# OpticalBoardRev2.net
KiCad netlist of a schematic drawn in EAGLE
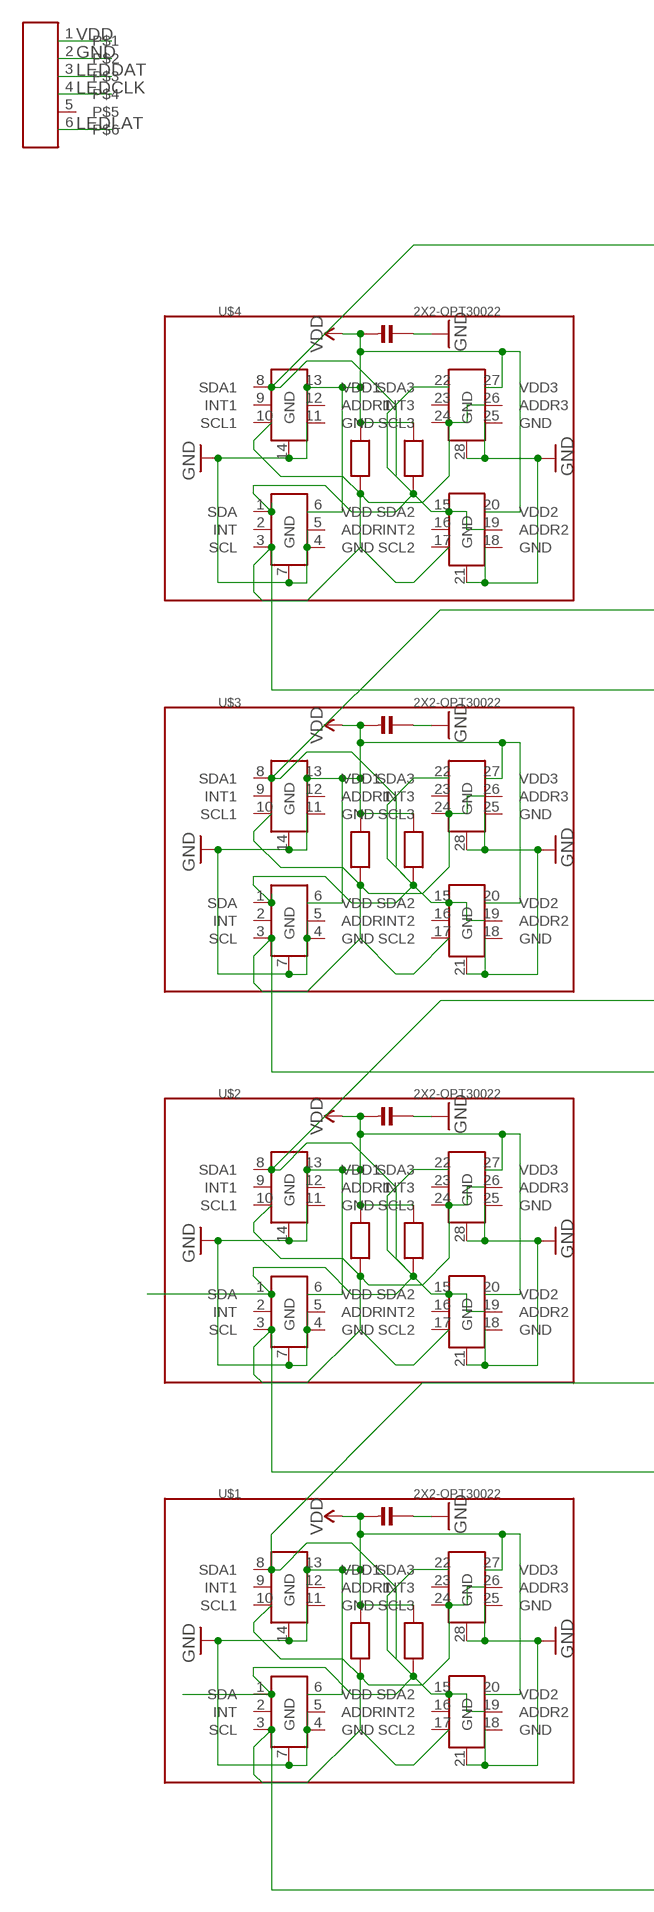
[diagram p0: schematic, sheet 1, part 1 of 2]
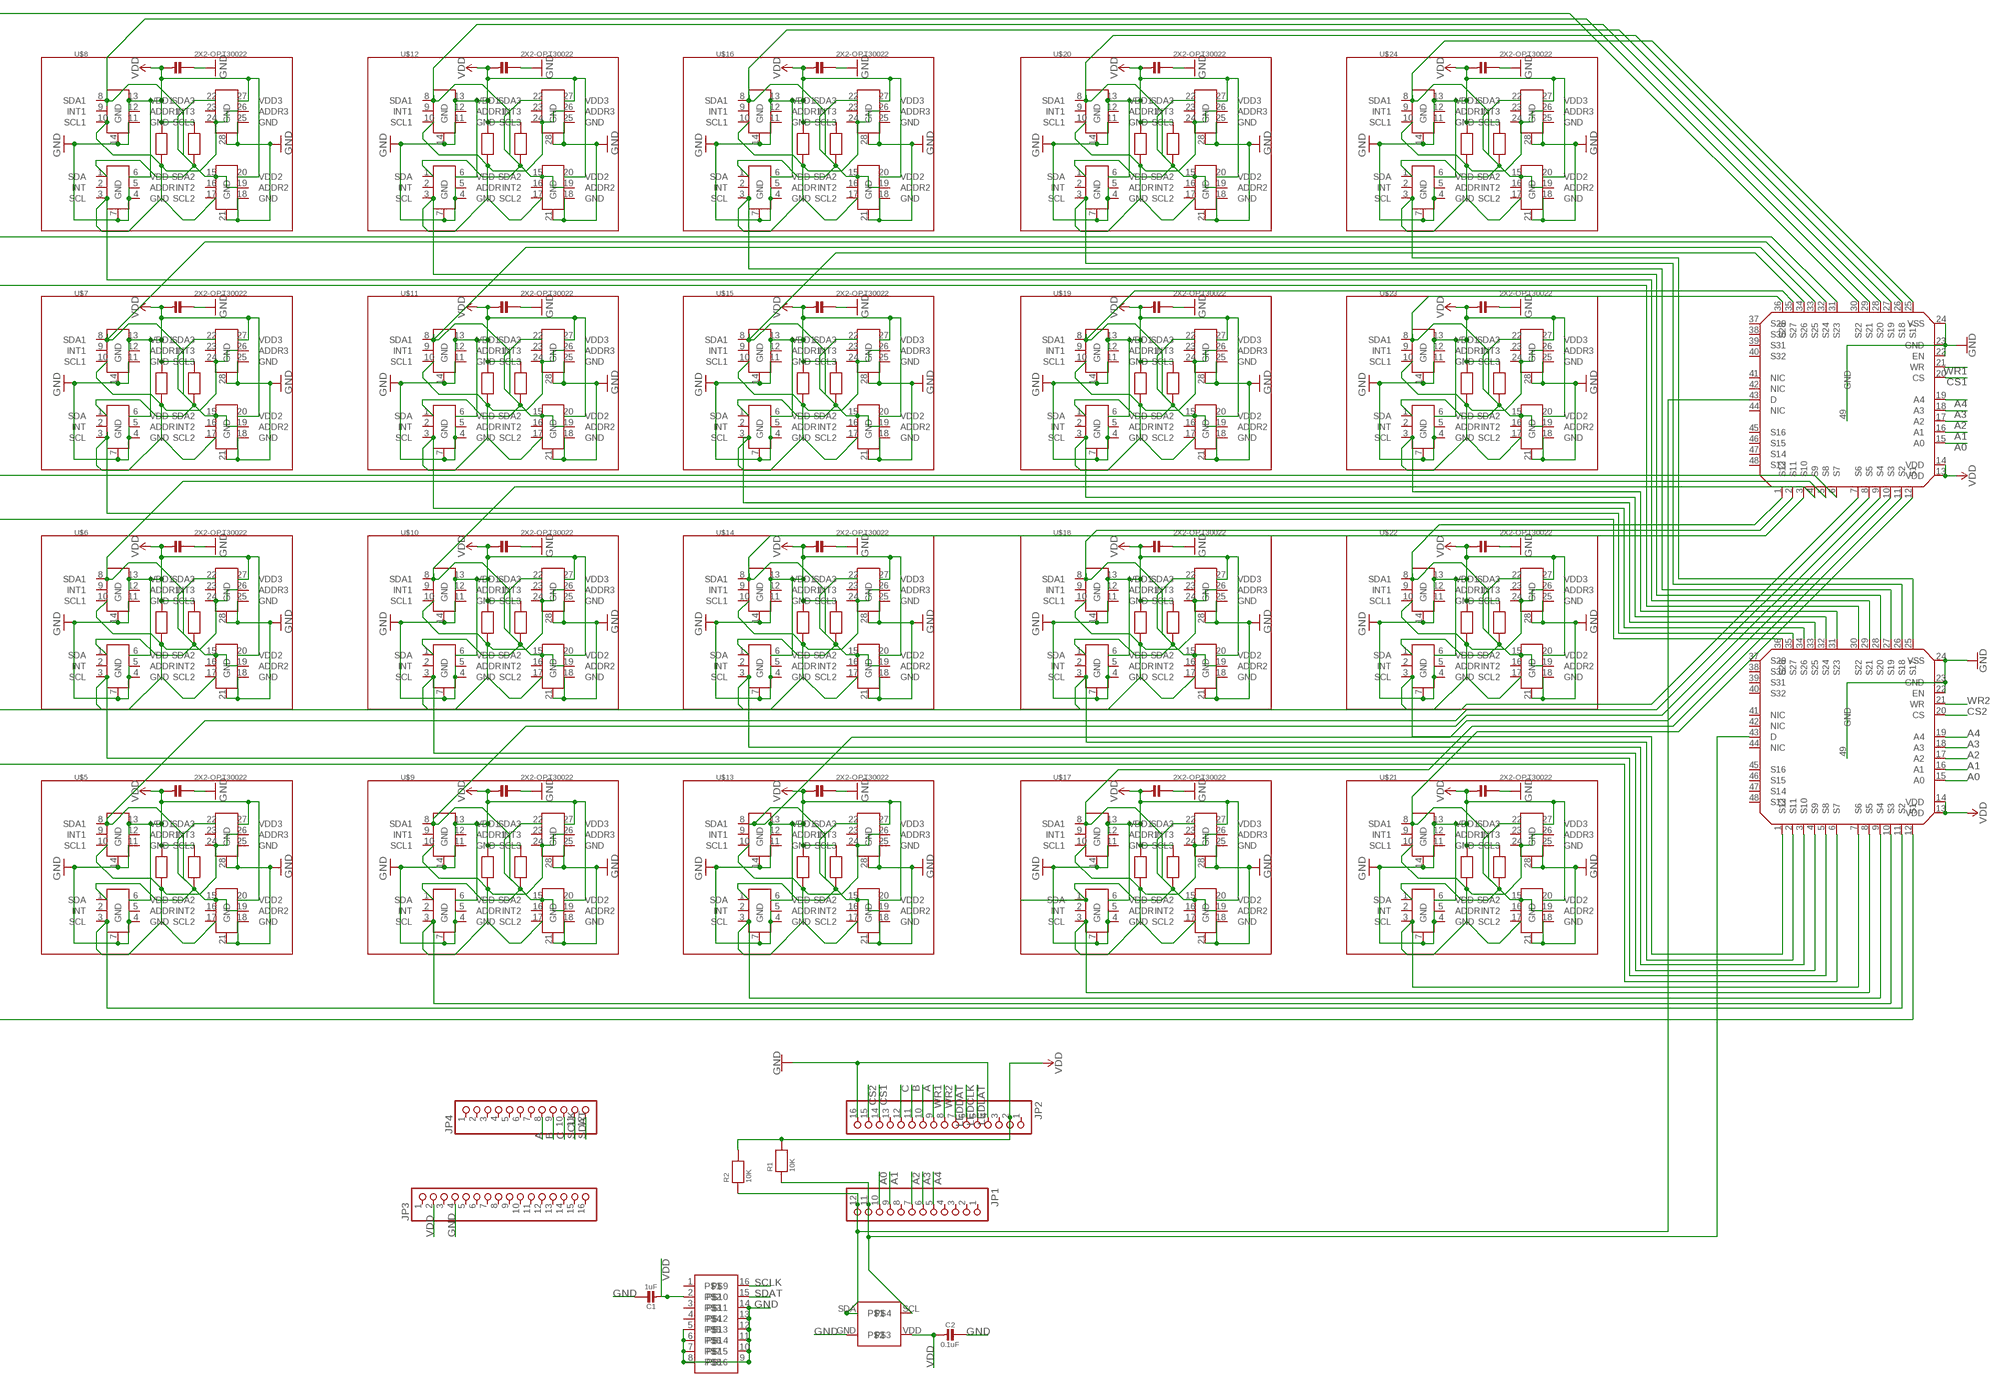
[diagram p1: schematic, sheet 1, part 2 of 2]

(export (version "E")
  (design (tool "Eeschema 10.0.6"))
  (components
    (comp (ref "C1")
      (value "1uF")
      (footprint "eagle-import:_0805")
      (libsource (lib "eagle-import") (part "CAP_CERAMIC_0805"))
    )
    (comp (ref "C2")
      (value "0.1uF")
      (footprint "eagle-import:_0805")
      (libsource (lib "eagle-import") (part "CAP_CERAMIC_0805"))
    )
    (comp (ref "JP1")
      (value "HEADER-1X12")
      (footprint "eagle-import:1X12_ROUND")
      (libsource (lib "eagle-import") (part "HEADER-1X12"))
    )
    (comp (ref "JP2")
      (value "HEADER-1X16ROUND")
      (footprint "eagle-import:1X16_ROUND")
      (libsource (lib "eagle-import") (part "HEADER-1X16ROUND"))
    )
    (comp (ref "JP3")
      (value "HEADER-1X16ROUND")
      (footprint "eagle-import:1X16_ROUND")
      (libsource (lib "eagle-import") (part "HEADER-1X16ROUND"))
    )
    (comp (ref "JP4")
      (value "HEADER-1X12")
      (footprint "eagle-import:1X12_ROUND")
      (libsource (lib "eagle-import") (part "HEADER-1X12"))
    )
    (comp (ref "R1")
      (value "10K")
      (footprint "eagle-import:_0805")
      (libsource (lib "eagle-import") (part "RESISTOR_0805"))
    )
    (comp (ref "R2")
      (value "10K")
      (footprint "eagle-import:_0805")
      (libsource (lib "eagle-import") (part "RESISTOR_0805"))
    )
    (comp (ref "U$1")
      (value "2X2-OPT30022")
      (footprint "eagle-import:2X2-OPT3002-2")
      (libsource (lib "eagle-import") (part "2X2-OPT30022"))
    )
    (comp (ref "U$2")
      (value "2X2-OPT30022")
      (footprint "eagle-import:2X2-OPT3002-2")
      (libsource (lib "eagle-import") (part "2X2-OPT30022"))
    )
    (comp (ref "U$3")
      (value "2X2-OPT30022")
      (footprint "eagle-import:2X2-OPT3002-2")
      (libsource (lib "eagle-import") (part "2X2-OPT30022"))
    )
    (comp (ref "U$4")
      (value "2X2-OPT30022")
      (footprint "eagle-import:2X2-OPT3002-2")
      (libsource (lib "eagle-import") (part "2X2-OPT30022"))
    )
    (comp (ref "U$5")
      (value "2X2-OPT30022")
      (footprint "eagle-import:2X2-OPT3002-2")
      (libsource (lib "eagle-import") (part "2X2-OPT30022"))
    )
    (comp (ref "U$6")
      (value "2X2-OPT30022")
      (footprint "eagle-import:2X2-OPT3002-2")
      (libsource (lib "eagle-import") (part "2X2-OPT30022"))
    )
    (comp (ref "U$7")
      (value "2X2-OPT30022")
      (footprint "eagle-import:2X2-OPT3002-2")
      (libsource (lib "eagle-import") (part "2X2-OPT30022"))
    )
    (comp (ref "U$8")
      (value "2X2-OPT30022")
      (footprint "eagle-import:2X2-OPT3002-2")
      (libsource (lib "eagle-import") (part "2X2-OPT30022"))
    )
    (comp (ref "U$9")
      (value "2X2-OPT30022")
      (footprint "eagle-import:2X2-OPT3002-2")
      (libsource (lib "eagle-import") (part "2X2-OPT30022"))
    )
    (comp (ref "U$10")
      (value "2X2-OPT30022")
      (footprint "eagle-import:2X2-OPT3002-2")
      (libsource (lib "eagle-import") (part "2X2-OPT30022"))
    )
    (comp (ref "U$11")
      (value "2X2-OPT30022")
      (footprint "eagle-import:2X2-OPT3002-2")
      (libsource (lib "eagle-import") (part "2X2-OPT30022"))
    )
    (comp (ref "U$12")
      (value "2X2-OPT30022")
      (footprint "eagle-import:2X2-OPT3002-2")
      (libsource (lib "eagle-import") (part "2X2-OPT30022"))
    )
    (comp (ref "U$13")
      (value "2X2-OPT30022")
      (footprint "eagle-import:2X2-OPT3002-2")
      (libsource (lib "eagle-import") (part "2X2-OPT30022"))
    )
    (comp (ref "U$14")
      (value "2X2-OPT30022")
      (footprint "eagle-import:2X2-OPT3002-2")
      (libsource (lib "eagle-import") (part "2X2-OPT30022"))
    )
    (comp (ref "U$15")
      (value "2X2-OPT30022")
      (footprint "eagle-import:2X2-OPT3002-2")
      (libsource (lib "eagle-import") (part "2X2-OPT30022"))
    )
    (comp (ref "U$16")
      (value "2X2-OPT30022")
      (footprint "eagle-import:2X2-OPT3002-2")
      (libsource (lib "eagle-import") (part "2X2-OPT30022"))
    )
    (comp (ref "U$17")
      (value "2X2-OPT30022")
      (footprint "eagle-import:2X2-OPT3002-2")
      (libsource (lib "eagle-import") (part "2X2-OPT30022"))
    )
    (comp (ref "U$18")
      (value "2X2-OPT30022")
      (footprint "eagle-import:2X2-OPT3002-2")
      (libsource (lib "eagle-import") (part "2X2-OPT30022"))
    )
    (comp (ref "U$19")
      (value "2X2-OPT30022")
      (footprint "eagle-import:2X2-OPT3002-2")
      (libsource (lib "eagle-import") (part "2X2-OPT30022"))
    )
    (comp (ref "U$20")
      (value "2X2-OPT30022")
      (footprint "eagle-import:2X2-OPT3002-2")
      (libsource (lib "eagle-import") (part "2X2-OPT30022"))
    )
    (comp (ref "U$21")
      (value "2X2-OPT30022")
      (footprint "eagle-import:2X2-OPT3002-2")
      (libsource (lib "eagle-import") (part "2X2-OPT30022"))
    )
    (comp (ref "U$22")
      (value "2X2-OPT30022")
      (footprint "eagle-import:2X2-OPT3002-2")
      (libsource (lib "eagle-import") (part "2X2-OPT30022"))
    )
    (comp (ref "U$23")
      (value "2X2-OPT30022")
      (footprint "eagle-import:2X2-OPT3002-2")
      (libsource (lib "eagle-import") (part "2X2-OPT30022"))
    )
    (comp (ref "U$24")
      (value "2X2-OPT30022")
      (footprint "eagle-import:2X2-OPT3002-2")
      (libsource (lib "eagle-import") (part "2X2-OPT30022"))
    )
    (comp (ref "U$25")
      (value "CONNECTOR_6PIN")
      (footprint "eagle-import:CONNECTOR_6PIN")
      (libsource (lib "eagle-import") (part "CONNECTOR_6PIN"))
    )
    (comp (ref "U$26")
      (value "32MUXTOP")
      (footprint "eagle-import:32MUX")
      (libsource (lib "eagle-import") (part "32MUXTOP"))
    )
    (comp (ref "U$27")
      (value "32MUXBOT")
      (footprint "eagle-import:32MUX_BOT")
      (libsource (lib "eagle-import") (part "32MUXBOT"))
    )
    (comp (ref "U$28")
      (value "RTC")
      (footprint "eagle-import:RTC")
      (libsource (lib "eagle-import") (part "RTC"))
    )
    (comp (ref "U$29")
      (value "TH_NEW")
      (footprint "eagle-import:TH_NEW")
      (libsource (lib "eagle-import") (part "TH_NEW"))
    )
  )
  (nets
    (net (code "1") (name "/A") (class "Default")
      (node (ref "JP2") (pin "10") (pinfunction "10_10") (pintype "passive"))
      (node (ref "JP4") (pin "8") (pinfunction "8_8") (pintype "passive"))
    )
    (net (code "2") (name "/A0") (class "Default")
      (node (ref "JP1") (pin "10") (pinfunction "10_10") (pintype "passive"))
      (node (ref "U$26") (pin "15") (pinfunction "A0_15") (pintype "bidirectional"))
      (node (ref "U$27") (pin "15") (pinfunction "A0_15") (pintype "bidirectional"))
    )
    (net (code "3") (name "/A1") (class "Default")
      (node (ref "JP1") (pin "9") (pinfunction "9_9") (pintype "passive"))
      (node (ref "U$26") (pin "16") (pinfunction "A1_16") (pintype "bidirectional"))
      (node (ref "U$27") (pin "16") (pinfunction "A1_16") (pintype "bidirectional"))
    )
    (net (code "4") (name "/A2") (class "Default")
      (node (ref "JP1") (pin "7") (pinfunction "7_7") (pintype "passive"))
      (node (ref "U$26") (pin "17") (pinfunction "A2_17") (pintype "bidirectional"))
      (node (ref "U$27") (pin "17") (pinfunction "A2_17") (pintype "bidirectional"))
    )
    (net (code "5") (name "/A3") (class "Default")
      (node (ref "JP1") (pin "6") (pinfunction "6_6") (pintype "passive"))
      (node (ref "U$26") (pin "18") (pinfunction "A3_18") (pintype "bidirectional"))
      (node (ref "U$27") (pin "18") (pinfunction "A3_18") (pintype "bidirectional"))
    )
    (net (code "6") (name "/A4") (class "Default")
      (node (ref "JP1") (pin "5") (pinfunction "5_5") (pintype "passive"))
      (node (ref "U$26") (pin "19") (pinfunction "A4_19") (pintype "bidirectional"))
      (node (ref "U$27") (pin "19") (pinfunction "A4_19") (pintype "bidirectional"))
    )
    (net (code "7") (name "/B") (class "Default")
      (node (ref "JP2") (pin "11") (pinfunction "11_11") (pintype "passive"))
      (node (ref "JP4") (pin "9") (pinfunction "9_9") (pintype "passive"))
    )
    (net (code "8") (name "/C") (class "Default")
      (node (ref "JP2") (pin "12") (pinfunction "12_12") (pintype "passive"))
      (node (ref "JP4") (pin "10") (pinfunction "10_10") (pintype "passive"))
    )
    (net (code "9") (name "/CS1") (class "Default")
      (node (ref "JP2") (pin "14") (pinfunction "14_14") (pintype "passive"))
      (node (ref "U$26") (pin "20") (pinfunction "CS_20") (pintype "bidirectional"))
    )
    (net (code "10") (name "/CS2") (class "Default")
      (node (ref "JP2") (pin "15") (pinfunction "15_15") (pintype "passive"))
      (node (ref "U$27") (pin "20") (pinfunction "CS_20") (pintype "bidirectional"))
    )
    (net (code "11") (name "/LEDCLK") (class "Default")
      (node (ref "JP2") (pin "6") (pinfunction "6_6") (pintype "passive"))
      (node (ref "U$25") (pin "4") (pinfunction "P$4_4") (pintype "bidirectional"))
    )
    (net (code "12") (name "/LEDDAT") (class "Default")
      (node (ref "JP2") (pin "7") (pinfunction "7_7") (pintype "passive"))
      (node (ref "U$25") (pin "3") (pinfunction "P$3_3") (pintype "bidirectional"))
    )
    (net (code "13") (name "/LEDLAT") (class "Default")
      (node (ref "JP2") (pin "5") (pinfunction "5_5") (pintype "passive"))
      (node (ref "U$25") (pin "6") (pinfunction "P$6_6") (pintype "bidirectional"))
    )
    (net (code "14") (name "/SCLK") (class "Default")
      (node (ref "JP1") (pin "11") (pinfunction "11_11") (pintype "passive"))
      (node (ref "JP4") (pin "11") (pinfunction "11_11") (pintype "passive"))
      (node (ref "R1") (pin "1") (pinfunction "1_1") (pintype "passive"))
      (node (ref "U$27") (pin "43") (pinfunction "D_43") (pintype "bidirectional"))
      (node (ref "U$28") (pin "16") (pinfunction "P$9_16") (pintype "bidirectional"))
      (node (ref "U$29") (pin "SCL") (pinfunction "P$4_SCL") (pintype "bidirectional"))
    )
    (net (code "15") (name "/SDAT") (class "Default")
      (node (ref "JP1") (pin "12") (pinfunction "12_12") (pintype "passive"))
      (node (ref "JP4") (pin "12") (pinfunction "12_12") (pintype "passive"))
      (node (ref "R2") (pin "1") (pinfunction "1_1") (pintype "passive"))
      (node (ref "U$26") (pin "43") (pinfunction "D_43") (pintype "bidirectional"))
      (node (ref "U$28") (pin "15") (pinfunction "P$10_15") (pintype "bidirectional"))
      (node (ref "U$29") (pin "SDA") (pinfunction "P$1_SDA") (pintype "bidirectional"))
    )
    (net (code "16") (name "/WR1") (class "Default")
      (node (ref "JP2") (pin "9") (pinfunction "9_9") (pintype "passive"))
      (node (ref "U$26") (pin "21") (pinfunction "WR_21") (pintype "bidirectional"))
    )
    (net (code "17") (name "/WR2") (class "Default")
      (node (ref "JP2") (pin "8") (pinfunction "8_8") (pintype "passive"))
      (node (ref "U$27") (pin "21") (pinfunction "WR_21") (pintype "bidirectional"))
    )
    (net (code "18") (name "GND") (class "Default")
      (node (ref "C1") (pin "1") (pinfunction "1_1") (pintype "passive"))
      (node (ref "C2") (pin "1") (pinfunction "1_1") (pintype "passive"))
      (node (ref "JP2") (pin "16") (pinfunction "16_16") (pintype "passive"))
      (node (ref "JP2") (pin "4") (pinfunction "4_4") (pintype "passive"))
      (node (ref "JP3") (pin "4") (pinfunction "4_4") (pintype "passive"))
      (node (ref "U$1") (pin "11") (pinfunction "GND_11") (pintype "bidirectional"))
      (node (ref "U$1") (pin "14") (pinfunction "GND_14") (pintype "bidirectional"))
      (node (ref "U$1") (pin "18") (pinfunction "GND_18") (pintype "bidirectional"))
      (node (ref "U$1") (pin "21") (pinfunction "GND_21") (pintype "bidirectional"))
      (node (ref "U$1") (pin "25") (pinfunction "GND_25") (pintype "bidirectional"))
      (node (ref "U$1") (pin "28") (pinfunction "GND_28") (pintype "bidirectional"))
      (node (ref "U$1") (pin "30") (pinfunction "GND_30") (pintype "passive"))
      (node (ref "U$1") (pin "4") (pinfunction "GND_4") (pintype "bidirectional"))
      (node (ref "U$1") (pin "5") (pinfunction "ADDR_5") (pintype "bidirectional"))
      (node (ref "U$1") (pin "7") (pinfunction "GND_7") (pintype "bidirectional"))
      (node (ref "U$10") (pin "11") (pinfunction "GND_11") (pintype "bidirectional"))
      (node (ref "U$10") (pin "14") (pinfunction "GND_14") (pintype "bidirectional"))
      (node (ref "U$10") (pin "18") (pinfunction "GND_18") (pintype "bidirectional"))
      (node (ref "U$10") (pin "21") (pinfunction "GND_21") (pintype "bidirectional"))
      (node (ref "U$10") (pin "25") (pinfunction "GND_25") (pintype "bidirectional"))
      (node (ref "U$10") (pin "28") (pinfunction "GND_28") (pintype "bidirectional"))
      (node (ref "U$10") (pin "30") (pinfunction "GND_30") (pintype "passive"))
      (node (ref "U$10") (pin "4") (pinfunction "GND_4") (pintype "bidirectional"))
      (node (ref "U$10") (pin "5") (pinfunction "ADDR_5") (pintype "bidirectional"))
      (node (ref "U$10") (pin "7") (pinfunction "GND_7") (pintype "bidirectional"))
      (node (ref "U$11") (pin "11") (pinfunction "GND_11") (pintype "bidirectional"))
      (node (ref "U$11") (pin "14") (pinfunction "GND_14") (pintype "bidirectional"))
      (node (ref "U$11") (pin "18") (pinfunction "GND_18") (pintype "bidirectional"))
      (node (ref "U$11") (pin "21") (pinfunction "GND_21") (pintype "bidirectional"))
      (node (ref "U$11") (pin "25") (pinfunction "GND_25") (pintype "bidirectional"))
      (node (ref "U$11") (pin "28") (pinfunction "GND_28") (pintype "bidirectional"))
      (node (ref "U$11") (pin "30") (pinfunction "GND_30") (pintype "passive"))
      (node (ref "U$11") (pin "4") (pinfunction "GND_4") (pintype "bidirectional"))
      (node (ref "U$11") (pin "5") (pinfunction "ADDR_5") (pintype "bidirectional"))
      (node (ref "U$11") (pin "7") (pinfunction "GND_7") (pintype "bidirectional"))
      (node (ref "U$12") (pin "11") (pinfunction "GND_11") (pintype "bidirectional"))
      (node (ref "U$12") (pin "14") (pinfunction "GND_14") (pintype "bidirectional"))
      (node (ref "U$12") (pin "18") (pinfunction "GND_18") (pintype "bidirectional"))
      (node (ref "U$12") (pin "21") (pinfunction "GND_21") (pintype "bidirectional"))
      (node (ref "U$12") (pin "25") (pinfunction "GND_25") (pintype "bidirectional"))
      (node (ref "U$12") (pin "28") (pinfunction "GND_28") (pintype "bidirectional"))
      (node (ref "U$12") (pin "30") (pinfunction "GND_30") (pintype "passive"))
      (node (ref "U$12") (pin "4") (pinfunction "GND_4") (pintype "bidirectional"))
      (node (ref "U$12") (pin "5") (pinfunction "ADDR_5") (pintype "bidirectional"))
      (node (ref "U$12") (pin "7") (pinfunction "GND_7") (pintype "bidirectional"))
      (node (ref "U$13") (pin "11") (pinfunction "GND_11") (pintype "bidirectional"))
      (node (ref "U$13") (pin "14") (pinfunction "GND_14") (pintype "bidirectional"))
      (node (ref "U$13") (pin "18") (pinfunction "GND_18") (pintype "bidirectional"))
      (node (ref "U$13") (pin "21") (pinfunction "GND_21") (pintype "bidirectional"))
      (node (ref "U$13") (pin "25") (pinfunction "GND_25") (pintype "bidirectional"))
      (node (ref "U$13") (pin "28") (pinfunction "GND_28") (pintype "bidirectional"))
      (node (ref "U$13") (pin "30") (pinfunction "GND_30") (pintype "passive"))
      (node (ref "U$13") (pin "4") (pinfunction "GND_4") (pintype "bidirectional"))
      (node (ref "U$13") (pin "5") (pinfunction "ADDR_5") (pintype "bidirectional"))
      (node (ref "U$13") (pin "7") (pinfunction "GND_7") (pintype "bidirectional"))
      (node (ref "U$14") (pin "11") (pinfunction "GND_11") (pintype "bidirectional"))
      (node (ref "U$14") (pin "14") (pinfunction "GND_14") (pintype "bidirectional"))
      (node (ref "U$14") (pin "18") (pinfunction "GND_18") (pintype "bidirectional"))
      (node (ref "U$14") (pin "21") (pinfunction "GND_21") (pintype "bidirectional"))
      (node (ref "U$14") (pin "25") (pinfunction "GND_25") (pintype "bidirectional"))
      (node (ref "U$14") (pin "28") (pinfunction "GND_28") (pintype "bidirectional"))
      (node (ref "U$14") (pin "30") (pinfunction "GND_30") (pintype "passive"))
      (node (ref "U$14") (pin "4") (pinfunction "GND_4") (pintype "bidirectional"))
      (node (ref "U$14") (pin "5") (pinfunction "ADDR_5") (pintype "bidirectional"))
      (node (ref "U$14") (pin "7") (pinfunction "GND_7") (pintype "bidirectional"))
      (node (ref "U$15") (pin "11") (pinfunction "GND_11") (pintype "bidirectional"))
      (node (ref "U$15") (pin "14") (pinfunction "GND_14") (pintype "bidirectional"))
      (node (ref "U$15") (pin "18") (pinfunction "GND_18") (pintype "bidirectional"))
      (node (ref "U$15") (pin "21") (pinfunction "GND_21") (pintype "bidirectional"))
      (node (ref "U$15") (pin "25") (pinfunction "GND_25") (pintype "bidirectional"))
      (node (ref "U$15") (pin "28") (pinfunction "GND_28") (pintype "bidirectional"))
      (node (ref "U$15") (pin "30") (pinfunction "GND_30") (pintype "passive"))
      (node (ref "U$15") (pin "4") (pinfunction "GND_4") (pintype "bidirectional"))
      (node (ref "U$15") (pin "5") (pinfunction "ADDR_5") (pintype "bidirectional"))
      (node (ref "U$15") (pin "7") (pinfunction "GND_7") (pintype "bidirectional"))
      (node (ref "U$16") (pin "11") (pinfunction "GND_11") (pintype "bidirectional"))
      (node (ref "U$16") (pin "14") (pinfunction "GND_14") (pintype "bidirectional"))
      (node (ref "U$16") (pin "18") (pinfunction "GND_18") (pintype "bidirectional"))
      (node (ref "U$16") (pin "21") (pinfunction "GND_21") (pintype "bidirectional"))
      (node (ref "U$16") (pin "25") (pinfunction "GND_25") (pintype "bidirectional"))
      (node (ref "U$16") (pin "28") (pinfunction "GND_28") (pintype "bidirectional"))
      (node (ref "U$16") (pin "30") (pinfunction "GND_30") (pintype "passive"))
      (node (ref "U$16") (pin "4") (pinfunction "GND_4") (pintype "bidirectional"))
      (node (ref "U$16") (pin "5") (pinfunction "ADDR_5") (pintype "bidirectional"))
      (node (ref "U$16") (pin "7") (pinfunction "GND_7") (pintype "bidirectional"))
      (node (ref "U$17") (pin "11") (pinfunction "GND_11") (pintype "bidirectional"))
      (node (ref "U$17") (pin "14") (pinfunction "GND_14") (pintype "bidirectional"))
      (node (ref "U$17") (pin "18") (pinfunction "GND_18") (pintype "bidirectional"))
      (node (ref "U$17") (pin "21") (pinfunction "GND_21") (pintype "bidirectional"))
      (node (ref "U$17") (pin "25") (pinfunction "GND_25") (pintype "bidirectional"))
      (node (ref "U$17") (pin "28") (pinfunction "GND_28") (pintype "bidirectional"))
      (node (ref "U$17") (pin "30") (pinfunction "GND_30") (pintype "passive"))
      (node (ref "U$17") (pin "4") (pinfunction "GND_4") (pintype "bidirectional"))
      (node (ref "U$17") (pin "5") (pinfunction "ADDR_5") (pintype "bidirectional"))
      (node (ref "U$17") (pin "7") (pinfunction "GND_7") (pintype "bidirectional"))
      (node (ref "U$18") (pin "11") (pinfunction "GND_11") (pintype "bidirectional"))
      (node (ref "U$18") (pin "14") (pinfunction "GND_14") (pintype "bidirectional"))
      (node (ref "U$18") (pin "18") (pinfunction "GND_18") (pintype "bidirectional"))
      (node (ref "U$18") (pin "21") (pinfunction "GND_21") (pintype "bidirectional"))
      (node (ref "U$18") (pin "25") (pinfunction "GND_25") (pintype "bidirectional"))
      (node (ref "U$18") (pin "28") (pinfunction "GND_28") (pintype "bidirectional"))
      (node (ref "U$18") (pin "30") (pinfunction "GND_30") (pintype "passive"))
      (node (ref "U$18") (pin "4") (pinfunction "GND_4") (pintype "bidirectional"))
      (node (ref "U$18") (pin "5") (pinfunction "ADDR_5") (pintype "bidirectional"))
      (node (ref "U$18") (pin "7") (pinfunction "GND_7") (pintype "bidirectional"))
      (node (ref "U$19") (pin "11") (pinfunction "GND_11") (pintype "bidirectional"))
      (node (ref "U$19") (pin "14") (pinfunction "GND_14") (pintype "bidirectional"))
      (node (ref "U$19") (pin "18") (pinfunction "GND_18") (pintype "bidirectional"))
      (node (ref "U$19") (pin "21") (pinfunction "GND_21") (pintype "bidirectional"))
      (node (ref "U$19") (pin "25") (pinfunction "GND_25") (pintype "bidirectional"))
      (node (ref "U$19") (pin "28") (pinfunction "GND_28") (pintype "bidirectional"))
      (node (ref "U$19") (pin "30") (pinfunction "GND_30") (pintype "passive"))
      (node (ref "U$19") (pin "4") (pinfunction "GND_4") (pintype "bidirectional"))
      (node (ref "U$19") (pin "5") (pinfunction "ADDR_5") (pintype "bidirectional"))
      (node (ref "U$19") (pin "7") (pinfunction "GND_7") (pintype "bidirectional"))
      (node (ref "U$2") (pin "11") (pinfunction "GND_11") (pintype "bidirectional"))
      (node (ref "U$2") (pin "14") (pinfunction "GND_14") (pintype "bidirectional"))
      (node (ref "U$2") (pin "18") (pinfunction "GND_18") (pintype "bidirectional"))
      (node (ref "U$2") (pin "21") (pinfunction "GND_21") (pintype "bidirectional"))
      (node (ref "U$2") (pin "25") (pinfunction "GND_25") (pintype "bidirectional"))
      (node (ref "U$2") (pin "28") (pinfunction "GND_28") (pintype "bidirectional"))
      (node (ref "U$2") (pin "30") (pinfunction "GND_30") (pintype "passive"))
      (node (ref "U$2") (pin "4") (pinfunction "GND_4") (pintype "bidirectional"))
      (node (ref "U$2") (pin "5") (pinfunction "ADDR_5") (pintype "bidirectional"))
      (node (ref "U$2") (pin "7") (pinfunction "GND_7") (pintype "bidirectional"))
      (node (ref "U$20") (pin "11") (pinfunction "GND_11") (pintype "bidirectional"))
      (node (ref "U$20") (pin "14") (pinfunction "GND_14") (pintype "bidirectional"))
      (node (ref "U$20") (pin "18") (pinfunction "GND_18") (pintype "bidirectional"))
      (node (ref "U$20") (pin "21") (pinfunction "GND_21") (pintype "bidirectional"))
      (node (ref "U$20") (pin "25") (pinfunction "GND_25") (pintype "bidirectional"))
      (node (ref "U$20") (pin "28") (pinfunction "GND_28") (pintype "bidirectional"))
      (node (ref "U$20") (pin "30") (pinfunction "GND_30") (pintype "passive"))
      (node (ref "U$20") (pin "4") (pinfunction "GND_4") (pintype "bidirectional"))
      (node (ref "U$20") (pin "5") (pinfunction "ADDR_5") (pintype "bidirectional"))
      (node (ref "U$20") (pin "7") (pinfunction "GND_7") (pintype "bidirectional"))
      (node (ref "U$21") (pin "11") (pinfunction "GND_11") (pintype "bidirectional"))
      (node (ref "U$21") (pin "14") (pinfunction "GND_14") (pintype "bidirectional"))
      (node (ref "U$21") (pin "18") (pinfunction "GND_18") (pintype "bidirectional"))
      (node (ref "U$21") (pin "21") (pinfunction "GND_21") (pintype "bidirectional"))
      (node (ref "U$21") (pin "25") (pinfunction "GND_25") (pintype "bidirectional"))
      (node (ref "U$21") (pin "28") (pinfunction "GND_28") (pintype "bidirectional"))
      (node (ref "U$21") (pin "30") (pinfunction "GND_30") (pintype "passive"))
      (node (ref "U$21") (pin "4") (pinfunction "GND_4") (pintype "bidirectional"))
      (node (ref "U$21") (pin "5") (pinfunction "ADDR_5") (pintype "bidirectional"))
      (node (ref "U$21") (pin "7") (pinfunction "GND_7") (pintype "bidirectional"))
      (node (ref "U$22") (pin "11") (pinfunction "GND_11") (pintype "bidirectional"))
      (node (ref "U$22") (pin "14") (pinfunction "GND_14") (pintype "bidirectional"))
      (node (ref "U$22") (pin "18") (pinfunction "GND_18") (pintype "bidirectional"))
      (node (ref "U$22") (pin "21") (pinfunction "GND_21") (pintype "bidirectional"))
      (node (ref "U$22") (pin "25") (pinfunction "GND_25") (pintype "bidirectional"))
      (node (ref "U$22") (pin "28") (pinfunction "GND_28") (pintype "bidirectional"))
      (node (ref "U$22") (pin "30") (pinfunction "GND_30") (pintype "passive"))
      (node (ref "U$22") (pin "4") (pinfunction "GND_4") (pintype "bidirectional"))
      (node (ref "U$22") (pin "5") (pinfunction "ADDR_5") (pintype "bidirectional"))
      (node (ref "U$22") (pin "7") (pinfunction "GND_7") (pintype "bidirectional"))
      (node (ref "U$23") (pin "11") (pinfunction "GND_11") (pintype "bidirectional"))
      (node (ref "U$23") (pin "14") (pinfunction "GND_14") (pintype "bidirectional"))
      (node (ref "U$23") (pin "18") (pinfunction "GND_18") (pintype "bidirectional"))
      (node (ref "U$23") (pin "21") (pinfunction "GND_21") (pintype "bidirectional"))
      (node (ref "U$23") (pin "25") (pinfunction "GND_25") (pintype "bidirectional"))
      (node (ref "U$23") (pin "28") (pinfunction "GND_28") (pintype "bidirectional"))
      (node (ref "U$23") (pin "30") (pinfunction "GND_30") (pintype "passive"))
      (node (ref "U$23") (pin "4") (pinfunction "GND_4") (pintype "bidirectional"))
      (node (ref "U$23") (pin "5") (pinfunction "ADDR_5") (pintype "bidirectional"))
      (node (ref "U$23") (pin "7") (pinfunction "GND_7") (pintype "bidirectional"))
      (node (ref "U$24") (pin "11") (pinfunction "GND_11") (pintype "bidirectional"))
      (node (ref "U$24") (pin "14") (pinfunction "GND_14") (pintype "bidirectional"))
      (node (ref "U$24") (pin "18") (pinfunction "GND_18") (pintype "bidirectional"))
      (node (ref "U$24") (pin "21") (pinfunction "GND_21") (pintype "bidirectional"))
      (node (ref "U$24") (pin "25") (pinfunction "GND_25") (pintype "bidirectional"))
      (node (ref "U$24") (pin "28") (pinfunction "GND_28") (pintype "bidirectional"))
      (node (ref "U$24") (pin "30") (pinfunction "GND_30") (pintype "passive"))
      (node (ref "U$24") (pin "4") (pinfunction "GND_4") (pintype "bidirectional"))
      (node (ref "U$24") (pin "5") (pinfunction "ADDR_5") (pintype "bidirectional"))
      (node (ref "U$24") (pin "7") (pinfunction "GND_7") (pintype "bidirectional"))
      (node (ref "U$25") (pin "2") (pinfunction "P$2_2") (pintype "bidirectional"))
      (node (ref "U$26") (pin "22") (pinfunction "EN_22") (pintype "bidirectional"))
      (node (ref "U$26") (pin "23") (pinfunction "GND_23") (pintype "bidirectional"))
      (node (ref "U$26") (pin "24") (pinfunction "VSS_24") (pintype "bidirectional"))
      (node (ref "U$26") (pin "49") (pinfunction "GND_49") (pintype "bidirectional"))
      (node (ref "U$27") (pin "22") (pinfunction "EN_22") (pintype "bidirectional"))
      (node (ref "U$27") (pin "23") (pinfunction "GND_23") (pintype "bidirectional"))
      (node (ref "U$27") (pin "24") (pinfunction "VSS_24") (pintype "bidirectional"))
      (node (ref "U$27") (pin "49") (pinfunction "GND_49") (pintype "bidirectional"))
      (node (ref "U$28") (pin "10") (pinfunction "P$15_10") (pintype "bidirectional"))
      (node (ref "U$28") (pin "11") (pinfunction "P$14_11") (pintype "bidirectional"))
      (node (ref "U$28") (pin "12") (pinfunction "P$13_12") (pintype "bidirectional"))
      (node (ref "U$28") (pin "13") (pinfunction "P$12_13") (pintype "bidirectional"))
      (node (ref "U$28") (pin "14") (pinfunction "P$11_14") (pintype "bidirectional"))
      (node (ref "U$28") (pin "5") (pinfunction "P$5_5") (pintype "bidirectional"))
      (node (ref "U$28") (pin "6") (pinfunction "P$6_6") (pintype "bidirectional"))
      (node (ref "U$28") (pin "7") (pinfunction "P$7_7") (pintype "bidirectional"))
      (node (ref "U$28") (pin "8") (pinfunction "P$8_8") (pintype "bidirectional"))
      (node (ref "U$28") (pin "9") (pinfunction "P$16_9") (pintype "bidirectional"))
      (node (ref "U$29") (pin "GND") (pinfunction "P$2_GND") (pintype "bidirectional"))
      (node (ref "U$3") (pin "11") (pinfunction "GND_11") (pintype "bidirectional"))
      (node (ref "U$3") (pin "14") (pinfunction "GND_14") (pintype "bidirectional"))
      (node (ref "U$3") (pin "18") (pinfunction "GND_18") (pintype "bidirectional"))
      (node (ref "U$3") (pin "21") (pinfunction "GND_21") (pintype "bidirectional"))
      (node (ref "U$3") (pin "25") (pinfunction "GND_25") (pintype "bidirectional"))
      (node (ref "U$3") (pin "28") (pinfunction "GND_28") (pintype "bidirectional"))
      (node (ref "U$3") (pin "30") (pinfunction "GND_30") (pintype "passive"))
      (node (ref "U$3") (pin "4") (pinfunction "GND_4") (pintype "bidirectional"))
      (node (ref "U$3") (pin "5") (pinfunction "ADDR_5") (pintype "bidirectional"))
      (node (ref "U$3") (pin "7") (pinfunction "GND_7") (pintype "bidirectional"))
      (node (ref "U$4") (pin "11") (pinfunction "GND_11") (pintype "bidirectional"))
      (node (ref "U$4") (pin "14") (pinfunction "GND_14") (pintype "bidirectional"))
      (node (ref "U$4") (pin "18") (pinfunction "GND_18") (pintype "bidirectional"))
      (node (ref "U$4") (pin "21") (pinfunction "GND_21") (pintype "bidirectional"))
      (node (ref "U$4") (pin "25") (pinfunction "GND_25") (pintype "bidirectional"))
      (node (ref "U$4") (pin "28") (pinfunction "GND_28") (pintype "bidirectional"))
      (node (ref "U$4") (pin "30") (pinfunction "GND_30") (pintype "passive"))
      (node (ref "U$4") (pin "4") (pinfunction "GND_4") (pintype "bidirectional"))
      (node (ref "U$4") (pin "5") (pinfunction "ADDR_5") (pintype "bidirectional"))
      (node (ref "U$4") (pin "7") (pinfunction "GND_7") (pintype "bidirectional"))
      (node (ref "U$5") (pin "11") (pinfunction "GND_11") (pintype "bidirectional"))
      (node (ref "U$5") (pin "14") (pinfunction "GND_14") (pintype "bidirectional"))
      (node (ref "U$5") (pin "18") (pinfunction "GND_18") (pintype "bidirectional"))
      (node (ref "U$5") (pin "21") (pinfunction "GND_21") (pintype "bidirectional"))
      (node (ref "U$5") (pin "25") (pinfunction "GND_25") (pintype "bidirectional"))
      (node (ref "U$5") (pin "28") (pinfunction "GND_28") (pintype "bidirectional"))
      (node (ref "U$5") (pin "30") (pinfunction "GND_30") (pintype "passive"))
      (node (ref "U$5") (pin "4") (pinfunction "GND_4") (pintype "bidirectional"))
      (node (ref "U$5") (pin "5") (pinfunction "ADDR_5") (pintype "bidirectional"))
      (node (ref "U$5") (pin "7") (pinfunction "GND_7") (pintype "bidirectional"))
      (node (ref "U$6") (pin "11") (pinfunction "GND_11") (pintype "bidirectional"))
      (node (ref "U$6") (pin "14") (pinfunction "GND_14") (pintype "bidirectional"))
      (node (ref "U$6") (pin "18") (pinfunction "GND_18") (pintype "bidirectional"))
      (node (ref "U$6") (pin "21") (pinfunction "GND_21") (pintype "bidirectional"))
      (node (ref "U$6") (pin "25") (pinfunction "GND_25") (pintype "bidirectional"))
      (node (ref "U$6") (pin "28") (pinfunction "GND_28") (pintype "bidirectional"))
      (node (ref "U$6") (pin "30") (pinfunction "GND_30") (pintype "passive"))
      (node (ref "U$6") (pin "4") (pinfunction "GND_4") (pintype "bidirectional"))
      (node (ref "U$6") (pin "5") (pinfunction "ADDR_5") (pintype "bidirectional"))
      (node (ref "U$6") (pin "7") (pinfunction "GND_7") (pintype "bidirectional"))
      (node (ref "U$7") (pin "11") (pinfunction "GND_11") (pintype "bidirectional"))
      (node (ref "U$7") (pin "14") (pinfunction "GND_14") (pintype "bidirectional"))
      (node (ref "U$7") (pin "18") (pinfunction "GND_18") (pintype "bidirectional"))
      (node (ref "U$7") (pin "21") (pinfunction "GND_21") (pintype "bidirectional"))
      (node (ref "U$7") (pin "25") (pinfunction "GND_25") (pintype "bidirectional"))
      (node (ref "U$7") (pin "28") (pinfunction "GND_28") (pintype "bidirectional"))
      (node (ref "U$7") (pin "30") (pinfunction "GND_30") (pintype "passive"))
      (node (ref "U$7") (pin "4") (pinfunction "GND_4") (pintype "bidirectional"))
      (node (ref "U$7") (pin "5") (pinfunction "ADDR_5") (pintype "bidirectional"))
      (node (ref "U$7") (pin "7") (pinfunction "GND_7") (pintype "bidirectional"))
      (node (ref "U$8") (pin "11") (pinfunction "GND_11") (pintype "bidirectional"))
      (node (ref "U$8") (pin "14") (pinfunction "GND_14") (pintype "bidirectional"))
      (node (ref "U$8") (pin "18") (pinfunction "GND_18") (pintype "bidirectional"))
      (node (ref "U$8") (pin "21") (pinfunction "GND_21") (pintype "bidirectional"))
      (node (ref "U$8") (pin "25") (pinfunction "GND_25") (pintype "bidirectional"))
      (node (ref "U$8") (pin "28") (pinfunction "GND_28") (pintype "bidirectional"))
      (node (ref "U$8") (pin "30") (pinfunction "GND_30") (pintype "passive"))
      (node (ref "U$8") (pin "4") (pinfunction "GND_4") (pintype "bidirectional"))
      (node (ref "U$8") (pin "5") (pinfunction "ADDR_5") (pintype "bidirectional"))
      (node (ref "U$8") (pin "7") (pinfunction "GND_7") (pintype "bidirectional"))
      (node (ref "U$9") (pin "11") (pinfunction "GND_11") (pintype "bidirectional"))
      (node (ref "U$9") (pin "14") (pinfunction "GND_14") (pintype "bidirectional"))
      (node (ref "U$9") (pin "18") (pinfunction "GND_18") (pintype "bidirectional"))
      (node (ref "U$9") (pin "21") (pinfunction "GND_21") (pintype "bidirectional"))
      (node (ref "U$9") (pin "25") (pinfunction "GND_25") (pintype "bidirectional"))
      (node (ref "U$9") (pin "28") (pinfunction "GND_28") (pintype "bidirectional"))
      (node (ref "U$9") (pin "30") (pinfunction "GND_30") (pintype "passive"))
      (node (ref "U$9") (pin "4") (pinfunction "GND_4") (pintype "bidirectional"))
      (node (ref "U$9") (pin "5") (pinfunction "ADDR_5") (pintype "bidirectional"))
      (node (ref "U$9") (pin "7") (pinfunction "GND_7") (pintype "bidirectional"))
    )
    (net (code "19") (name "Net-(U$1-ADDR2)") (class "Default")
      (node (ref "U$1") (pin "1") (pinfunction "SDA_1") (pintype "bidirectional"))
      (node (ref "U$1") (pin "15") (pinfunction "SDA2_15") (pintype "bidirectional"))
      (node (ref "U$1") (pin "19") (pinfunction "ADDR2_19") (pintype "bidirectional"))
      (node (ref "U$1") (pin "22") (pinfunction "SDA3_22") (pintype "bidirectional"))
      (node (ref "U$1") (pin "33") (pinfunction "R2+_33") (pintype "passive"))
      (node (ref "U$1") (pin "8") (pinfunction "SDA1_8") (pintype "bidirectional"))
      (node (ref "U$26") (pin "7") (pinfunction "S6_7") (pintype "bidirectional"))
    )
    (net (code "20") (name "Net-(U$1-ADDR3)") (class "Default")
      (node (ref "U$1") (pin "10") (pinfunction "SCL1_10") (pintype "bidirectional"))
      (node (ref "U$1") (pin "17") (pinfunction "SCL2_17") (pintype "bidirectional"))
      (node (ref "U$1") (pin "24") (pinfunction "SCL3_24") (pintype "bidirectional"))
      (node (ref "U$1") (pin "26") (pinfunction "ADDR3_26") (pintype "bidirectional"))
      (node (ref "U$1") (pin "3") (pinfunction "SCL_3") (pintype "bidirectional"))
      (node (ref "U$1") (pin "31") (pinfunction "R1+_31") (pintype "passive"))
      (node (ref "U$27") (pin "12") (pinfunction "S1_12") (pintype "bidirectional"))
    )
    (net (code "21") (name "Net-(U$2-ADDR2)") (class "Default")
      (node (ref "U$2") (pin "1") (pinfunction "SDA_1") (pintype "bidirectional"))
      (node (ref "U$2") (pin "15") (pinfunction "SDA2_15") (pintype "bidirectional"))
      (node (ref "U$2") (pin "19") (pinfunction "ADDR2_19") (pintype "bidirectional"))
      (node (ref "U$2") (pin "22") (pinfunction "SDA3_22") (pintype "bidirectional"))
      (node (ref "U$2") (pin "33") (pinfunction "R2+_33") (pintype "passive"))
      (node (ref "U$2") (pin "8") (pinfunction "SDA1_8") (pintype "bidirectional"))
      (node (ref "U$26") (pin "6") (pinfunction "S7_6") (pintype "bidirectional"))
    )
    (net (code "22") (name "Net-(U$2-ADDR3)") (class "Default")
      (node (ref "U$2") (pin "10") (pinfunction "SCL1_10") (pintype "bidirectional"))
      (node (ref "U$2") (pin "17") (pinfunction "SCL2_17") (pintype "bidirectional"))
      (node (ref "U$2") (pin "24") (pinfunction "SCL3_24") (pintype "bidirectional"))
      (node (ref "U$2") (pin "26") (pinfunction "ADDR3_26") (pintype "bidirectional"))
      (node (ref "U$2") (pin "3") (pinfunction "SCL_3") (pintype "bidirectional"))
      (node (ref "U$2") (pin "31") (pinfunction "R1+_31") (pintype "passive"))
      (node (ref "U$27") (pin "6") (pinfunction "S7_6") (pintype "bidirectional"))
    )
    (net (code "23") (name "Net-(U$10-ADDR2)") (class "Default")
      (node (ref "U$10") (pin "1") (pinfunction "SDA_1") (pintype "bidirectional"))
      (node (ref "U$10") (pin "15") (pinfunction "SDA2_15") (pintype "bidirectional"))
      (node (ref "U$10") (pin "19") (pinfunction "ADDR2_19") (pintype "bidirectional"))
      (node (ref "U$10") (pin "22") (pinfunction "SDA3_22") (pintype "bidirectional"))
      (node (ref "U$10") (pin "33") (pinfunction "R2+_33") (pintype "passive"))
      (node (ref "U$10") (pin "8") (pinfunction "SDA1_8") (pintype "bidirectional"))
      (node (ref "U$26") (pin "4") (pinfunction "S9_4") (pintype "bidirectional"))
    )
    (net (code "24") (name "Net-(U$10-ADDR3)") (class "Default")
      (node (ref "U$10") (pin "10") (pinfunction "SCL1_10") (pintype "bidirectional"))
      (node (ref "U$10") (pin "17") (pinfunction "SCL2_17") (pintype "bidirectional"))
      (node (ref "U$10") (pin "24") (pinfunction "SCL3_24") (pintype "bidirectional"))
      (node (ref "U$10") (pin "26") (pinfunction "ADDR3_26") (pintype "bidirectional"))
      (node (ref "U$10") (pin "3") (pinfunction "SCL_3") (pintype "bidirectional"))
      (node (ref "U$10") (pin "31") (pinfunction "R1+_31") (pintype "passive"))
      (node (ref "U$27") (pin "4") (pinfunction "S9_4") (pintype "bidirectional"))
    )
    (net (code "25") (name "Net-(U$11-ADDR2)") (class "Default")
      (node (ref "U$11") (pin "1") (pinfunction "SDA_1") (pintype "bidirectional"))
      (node (ref "U$11") (pin "15") (pinfunction "SDA2_15") (pintype "bidirectional"))
      (node (ref "U$11") (pin "19") (pinfunction "ADDR2_19") (pintype "bidirectional"))
      (node (ref "U$11") (pin "22") (pinfunction "SDA3_22") (pintype "bidirectional"))
      (node (ref "U$11") (pin "33") (pinfunction "R2+_33") (pintype "passive"))
      (node (ref "U$11") (pin "8") (pinfunction "SDA1_8") (pintype "bidirectional"))
      (node (ref "U$26") (pin "33") (pinfunction "S25_33") (pintype "bidirectional"))
    )
    (net (code "26") (name "Net-(U$11-ADDR3)") (class "Default")
      (node (ref "U$11") (pin "10") (pinfunction "SCL1_10") (pintype "bidirectional"))
      (node (ref "U$11") (pin "17") (pinfunction "SCL2_17") (pintype "bidirectional"))
      (node (ref "U$11") (pin "24") (pinfunction "SCL3_24") (pintype "bidirectional"))
      (node (ref "U$11") (pin "26") (pinfunction "ADDR3_26") (pintype "bidirectional"))
      (node (ref "U$11") (pin "3") (pinfunction "SCL_3") (pintype "bidirectional"))
      (node (ref "U$11") (pin "31") (pinfunction "R1+_31") (pintype "passive"))
      (node (ref "U$27") (pin "34") (pinfunction "S26_34") (pintype "bidirectional"))
    )
    (net (code "27") (name "Net-(U$12-ADDR2)") (class "Default")
      (node (ref "U$12") (pin "1") (pinfunction "SDA_1") (pintype "bidirectional"))
      (node (ref "U$12") (pin "15") (pinfunction "SDA2_15") (pintype "bidirectional"))
      (node (ref "U$12") (pin "19") (pinfunction "ADDR2_19") (pintype "bidirectional"))
      (node (ref "U$12") (pin "22") (pinfunction "SDA3_22") (pintype "bidirectional"))
      (node (ref "U$12") (pin "33") (pinfunction "R2+_33") (pintype "passive"))
      (node (ref "U$12") (pin "8") (pinfunction "SDA1_8") (pintype "bidirectional"))
      (node (ref "U$26") (pin "28") (pinfunction "S20_28") (pintype "bidirectional"))
    )
    (net (code "28") (name "Net-(U$12-ADDR3)") (class "Default")
      (node (ref "U$12") (pin "10") (pinfunction "SCL1_10") (pintype "bidirectional"))
      (node (ref "U$12") (pin "17") (pinfunction "SCL2_17") (pintype "bidirectional"))
      (node (ref "U$12") (pin "24") (pinfunction "SCL3_24") (pintype "bidirectional"))
      (node (ref "U$12") (pin "26") (pinfunction "ADDR3_26") (pintype "bidirectional"))
      (node (ref "U$12") (pin "3") (pinfunction "SCL_3") (pintype "bidirectional"))
      (node (ref "U$12") (pin "31") (pinfunction "R1+_31") (pintype "passive"))
      (node (ref "U$27") (pin "28") (pinfunction "S20_28") (pintype "bidirectional"))
    )
    (net (code "29") (name "Net-(U$13-ADDR2)") (class "Default")
      (node (ref "U$13") (pin "1") (pinfunction "SDA_1") (pintype "bidirectional"))
      (node (ref "U$13") (pin "15") (pinfunction "SDA2_15") (pintype "bidirectional"))
      (node (ref "U$13") (pin "19") (pinfunction "ADDR2_19") (pintype "bidirectional"))
      (node (ref "U$13") (pin "22") (pinfunction "SDA3_22") (pintype "bidirectional"))
      (node (ref "U$13") (pin "33") (pinfunction "R2+_33") (pintype "passive"))
      (node (ref "U$13") (pin "8") (pinfunction "SDA1_8") (pintype "bidirectional"))
      (node (ref "U$26") (pin "10") (pinfunction "S3_10") (pintype "bidirectional"))
    )
    (net (code "30") (name "Net-(U$13-ADDR3)") (class "Default")
      (node (ref "U$13") (pin "10") (pinfunction "SCL1_10") (pintype "bidirectional"))
      (node (ref "U$13") (pin "17") (pinfunction "SCL2_17") (pintype "bidirectional"))
      (node (ref "U$13") (pin "24") (pinfunction "SCL3_24") (pintype "bidirectional"))
      (node (ref "U$13") (pin "26") (pinfunction "ADDR3_26") (pintype "bidirectional"))
      (node (ref "U$13") (pin "3") (pinfunction "SCL_3") (pintype "bidirectional"))
      (node (ref "U$13") (pin "31") (pinfunction "R1+_31") (pintype "passive"))
      (node (ref "U$27") (pin "9") (pinfunction "S4_9") (pintype "bidirectional"))
    )
    (net (code "31") (name "Net-(U$14-ADDR2)") (class "Default")
      (node (ref "U$14") (pin "1") (pinfunction "SDA_1") (pintype "bidirectional"))
      (node (ref "U$14") (pin "15") (pinfunction "SDA2_15") (pintype "bidirectional"))
      (node (ref "U$14") (pin "19") (pinfunction "ADDR2_19") (pintype "bidirectional"))
      (node (ref "U$14") (pin "22") (pinfunction "SDA3_22") (pintype "bidirectional"))
      (node (ref "U$14") (pin "33") (pinfunction "R2+_33") (pintype "passive"))
      (node (ref "U$14") (pin "8") (pinfunction "SDA1_8") (pintype "bidirectional"))
      (node (ref "U$26") (pin "3") (pinfunction "S10_3") (pintype "bidirectional"))
    )
    (net (code "32") (name "Net-(U$14-ADDR3)") (class "Default")
      (node (ref "U$14") (pin "10") (pinfunction "SCL1_10") (pintype "bidirectional"))
      (node (ref "U$14") (pin "17") (pinfunction "SCL2_17") (pintype "bidirectional"))
      (node (ref "U$14") (pin "24") (pinfunction "SCL3_24") (pintype "bidirectional"))
      (node (ref "U$14") (pin "26") (pinfunction "ADDR3_26") (pintype "bidirectional"))
      (node (ref "U$14") (pin "3") (pinfunction "SCL_3") (pintype "bidirectional"))
      (node (ref "U$14") (pin "31") (pinfunction "R1+_31") (pintype "passive"))
      (node (ref "U$27") (pin "3") (pinfunction "S10_3") (pintype "bidirectional"))
    )
    (net (code "33") (name "Net-(U$15-ADDR2)") (class "Default")
      (node (ref "U$15") (pin "1") (pinfunction "SDA_1") (pintype "bidirectional"))
      (node (ref "U$15") (pin "15") (pinfunction "SDA2_15") (pintype "bidirectional"))
      (node (ref "U$15") (pin "19") (pinfunction "ADDR2_19") (pintype "bidirectional"))
      (node (ref "U$15") (pin "22") (pinfunction "SDA3_22") (pintype "bidirectional"))
      (node (ref "U$15") (pin "33") (pinfunction "R2+_33") (pintype "passive"))
      (node (ref "U$15") (pin "8") (pinfunction "SDA1_8") (pintype "bidirectional"))
      (node (ref "U$26") (pin "34") (pinfunction "S26_34") (pintype "bidirectional"))
    )
    (net (code "34") (name "Net-(U$15-ADDR3)") (class "Default")
      (node (ref "U$15") (pin "10") (pinfunction "SCL1_10") (pintype "bidirectional"))
      (node (ref "U$15") (pin "17") (pinfunction "SCL2_17") (pintype "bidirectional"))
      (node (ref "U$15") (pin "24") (pinfunction "SCL3_24") (pintype "bidirectional"))
      (node (ref "U$15") (pin "26") (pinfunction "ADDR3_26") (pintype "bidirectional"))
      (node (ref "U$15") (pin "3") (pinfunction "SCL_3") (pintype "bidirectional"))
      (node (ref "U$15") (pin "31") (pinfunction "R1+_31") (pintype "passive"))
      (node (ref "U$27") (pin "33") (pinfunction "S25_33") (pintype "bidirectional"))
    )
    (net (code "35") (name "Net-(U$16-ADDR2)") (class "Default")
      (node (ref "U$16") (pin "1") (pinfunction "SDA_1") (pintype "bidirectional"))
      (node (ref "U$16") (pin "15") (pinfunction "SDA2_15") (pintype "bidirectional"))
      (node (ref "U$16") (pin "19") (pinfunction "ADDR2_19") (pintype "bidirectional"))
      (node (ref "U$16") (pin "22") (pinfunction "SDA3_22") (pintype "bidirectional"))
      (node (ref "U$16") (pin "33") (pinfunction "R2+_33") (pintype "passive"))
      (node (ref "U$16") (pin "8") (pinfunction "SDA1_8") (pintype "bidirectional"))
      (node (ref "U$26") (pin "27") (pinfunction "S19_27") (pintype "bidirectional"))
    )
    (net (code "36") (name "Net-(U$16-ADDR3)") (class "Default")
      (node (ref "U$16") (pin "10") (pinfunction "SCL1_10") (pintype "bidirectional"))
      (node (ref "U$16") (pin "17") (pinfunction "SCL2_17") (pintype "bidirectional"))
      (node (ref "U$16") (pin "24") (pinfunction "SCL3_24") (pintype "bidirectional"))
      (node (ref "U$16") (pin "26") (pinfunction "ADDR3_26") (pintype "bidirectional"))
      (node (ref "U$16") (pin "3") (pinfunction "SCL_3") (pintype "bidirectional"))
      (node (ref "U$16") (pin "31") (pinfunction "R1+_31") (pintype "passive"))
      (node (ref "U$27") (pin "27") (pinfunction "S19_27") (pintype "bidirectional"))
    )
    (net (code "37") (name "Net-(U$17-ADDR2)") (class "Default")
      (node (ref "U$17") (pin "1") (pinfunction "SDA_1") (pintype "bidirectional"))
      (node (ref "U$17") (pin "15") (pinfunction "SDA2_15") (pintype "bidirectional"))
      (node (ref "U$17") (pin "19") (pinfunction "ADDR2_19") (pintype "bidirectional"))
      (node (ref "U$17") (pin "22") (pinfunction "SDA3_22") (pintype "bidirectional"))
      (node (ref "U$17") (pin "33") (pinfunction "R2+_33") (pintype "passive"))
      (node (ref "U$17") (pin "8") (pinfunction "SDA1_8") (pintype "bidirectional"))
      (node (ref "U$26") (pin "11") (pinfunction "S2_11") (pintype "bidirectional"))
    )
    (net (code "38") (name "Net-(U$17-ADDR3)") (class "Default")
      (node (ref "U$17") (pin "10") (pinfunction "SCL1_10") (pintype "bidirectional"))
      (node (ref "U$17") (pin "17") (pinfunction "SCL2_17") (pintype "bidirectional"))
      (node (ref "U$17") (pin "24") (pinfunction "SCL3_24") (pintype "bidirectional"))
      (node (ref "U$17") (pin "26") (pinfunction "ADDR3_26") (pintype "bidirectional"))
      (node (ref "U$17") (pin "3") (pinfunction "SCL_3") (pintype "bidirectional"))
      (node (ref "U$17") (pin "31") (pinfunction "R1+_31") (pintype "passive"))
      (node (ref "U$27") (pin "8") (pinfunction "S5_8") (pintype "bidirectional"))
    )
    (net (code "39") (name "Net-(U$18-ADDR2)") (class "Default")
      (node (ref "U$18") (pin "1") (pinfunction "SDA_1") (pintype "bidirectional"))
      (node (ref "U$18") (pin "15") (pinfunction "SDA2_15") (pintype "bidirectional"))
      (node (ref "U$18") (pin "19") (pinfunction "ADDR2_19") (pintype "bidirectional"))
      (node (ref "U$18") (pin "22") (pinfunction "SDA3_22") (pintype "bidirectional"))
      (node (ref "U$18") (pin "33") (pinfunction "R2+_33") (pintype "passive"))
      (node (ref "U$18") (pin "8") (pinfunction "SDA1_8") (pintype "bidirectional"))
      (node (ref "U$26") (pin "2") (pinfunction "S11_2") (pintype "bidirectional"))
    )
    (net (code "40") (name "Net-(U$18-ADDR3)") (class "Default")
      (node (ref "U$18") (pin "10") (pinfunction "SCL1_10") (pintype "bidirectional"))
      (node (ref "U$18") (pin "17") (pinfunction "SCL2_17") (pintype "bidirectional"))
      (node (ref "U$18") (pin "24") (pinfunction "SCL3_24") (pintype "bidirectional"))
      (node (ref "U$18") (pin "26") (pinfunction "ADDR3_26") (pintype "bidirectional"))
      (node (ref "U$18") (pin "3") (pinfunction "SCL_3") (pintype "bidirectional"))
      (node (ref "U$18") (pin "31") (pinfunction "R1+_31") (pintype "passive"))
      (node (ref "U$27") (pin "2") (pinfunction "S11_2") (pintype "bidirectional"))
    )
    (net (code "41") (name "Net-(U$19-ADDR2)") (class "Default")
      (node (ref "U$19") (pin "1") (pinfunction "SDA_1") (pintype "bidirectional"))
      (node (ref "U$19") (pin "15") (pinfunction "SDA2_15") (pintype "bidirectional"))
      (node (ref "U$19") (pin "19") (pinfunction "ADDR2_19") (pintype "bidirectional"))
      (node (ref "U$19") (pin "22") (pinfunction "SDA3_22") (pintype "bidirectional"))
      (node (ref "U$19") (pin "33") (pinfunction "R2+_33") (pintype "passive"))
      (node (ref "U$19") (pin "8") (pinfunction "SDA1_8") (pintype "bidirectional"))
      (node (ref "U$26") (pin "35") (pinfunction "S27_35") (pintype "bidirectional"))
    )
    (net (code "42") (name "Net-(U$19-ADDR3)") (class "Default")
      (node (ref "U$19") (pin "10") (pinfunction "SCL1_10") (pintype "bidirectional"))
      (node (ref "U$19") (pin "17") (pinfunction "SCL2_17") (pintype "bidirectional"))
      (node (ref "U$19") (pin "24") (pinfunction "SCL3_24") (pintype "bidirectional"))
      (node (ref "U$19") (pin "26") (pinfunction "ADDR3_26") (pintype "bidirectional"))
      (node (ref "U$19") (pin "3") (pinfunction "SCL_3") (pintype "bidirectional"))
      (node (ref "U$19") (pin "31") (pinfunction "R1+_31") (pintype "passive"))
      (node (ref "U$27") (pin "32") (pinfunction "S24_32") (pintype "bidirectional"))
    )
    (net (code "43") (name "Net-(U$20-ADDR2)") (class "Default")
      (node (ref "U$20") (pin "1") (pinfunction "SDA_1") (pintype "bidirectional"))
      (node (ref "U$20") (pin "15") (pinfunction "SDA2_15") (pintype "bidirectional"))
      (node (ref "U$20") (pin "19") (pinfunction "ADDR2_19") (pintype "bidirectional"))
      (node (ref "U$20") (pin "22") (pinfunction "SDA3_22") (pintype "bidirectional"))
      (node (ref "U$20") (pin "33") (pinfunction "R2+_33") (pintype "passive"))
      (node (ref "U$20") (pin "8") (pinfunction "SDA1_8") (pintype "bidirectional"))
      (node (ref "U$26") (pin "26") (pinfunction "S18_26") (pintype "bidirectional"))
    )
    (net (code "44") (name "Net-(U$20-ADDR3)") (class "Default")
      (node (ref "U$20") (pin "10") (pinfunction "SCL1_10") (pintype "bidirectional"))
      (node (ref "U$20") (pin "17") (pinfunction "SCL2_17") (pintype "bidirectional"))
      (node (ref "U$20") (pin "24") (pinfunction "SCL3_24") (pintype "bidirectional"))
      (node (ref "U$20") (pin "26") (pinfunction "ADDR3_26") (pintype "bidirectional"))
      (node (ref "U$20") (pin "3") (pinfunction "SCL_3") (pintype "bidirectional"))
      (node (ref "U$20") (pin "31") (pinfunction "R1+_31") (pintype "passive"))
      (node (ref "U$27") (pin "26") (pinfunction "S18_26") (pintype "bidirectional"))
    )
    (net (code "45") (name "Net-(U$21-ADDR2)") (class "Default")
      (node (ref "U$21") (pin "1") (pinfunction "SDA_1") (pintype "bidirectional"))
      (node (ref "U$21") (pin "15") (pinfunction "SDA2_15") (pintype "bidirectional"))
      (node (ref "U$21") (pin "19") (pinfunction "ADDR2_19") (pintype "bidirectional"))
      (node (ref "U$21") (pin "22") (pinfunction "SDA3_22") (pintype "bidirectional"))
      (node (ref "U$21") (pin "33") (pinfunction "R2+_33") (pintype "passive"))
      (node (ref "U$21") (pin "8") (pinfunction "SDA1_8") (pintype "bidirectional"))
      (node (ref "U$26") (pin "12") (pinfunction "S1_12") (pintype "bidirectional"))
    )
    (net (code "46") (name "Net-(U$21-ADDR3)") (class "Default")
      (node (ref "U$21") (pin "10") (pinfunction "SCL1_10") (pintype "bidirectional"))
      (node (ref "U$21") (pin "17") (pinfunction "SCL2_17") (pintype "bidirectional"))
      (node (ref "U$21") (pin "24") (pinfunction "SCL3_24") (pintype "bidirectional"))
      (node (ref "U$21") (pin "26") (pinfunction "ADDR3_26") (pintype "bidirectional"))
      (node (ref "U$21") (pin "3") (pinfunction "SCL_3") (pintype "bidirectional"))
      (node (ref "U$21") (pin "31") (pinfunction "R1+_31") (pintype "passive"))
      (node (ref "U$27") (pin "7") (pinfunction "S6_7") (pintype "bidirectional"))
    )
    (net (code "47") (name "Net-(U$22-ADDR2)") (class "Default")
      (node (ref "U$22") (pin "1") (pinfunction "SDA_1") (pintype "bidirectional"))
      (node (ref "U$22") (pin "15") (pinfunction "SDA2_15") (pintype "bidirectional"))
      (node (ref "U$22") (pin "19") (pinfunction "ADDR2_19") (pintype "bidirectional"))
      (node (ref "U$22") (pin "22") (pinfunction "SDA3_22") (pintype "bidirectional"))
      (node (ref "U$22") (pin "33") (pinfunction "R2+_33") (pintype "passive"))
      (node (ref "U$22") (pin "8") (pinfunction "SDA1_8") (pintype "bidirectional"))
      (node (ref "U$26") (pin "1") (pinfunction "S12_1") (pintype "bidirectional"))
    )
    (net (code "48") (name "Net-(U$22-ADDR3)") (class "Default")
      (node (ref "U$22") (pin "10") (pinfunction "SCL1_10") (pintype "bidirectional"))
      (node (ref "U$22") (pin "17") (pinfunction "SCL2_17") (pintype "bidirectional"))
      (node (ref "U$22") (pin "24") (pinfunction "SCL3_24") (pintype "bidirectional"))
      (node (ref "U$22") (pin "26") (pinfunction "ADDR3_26") (pintype "bidirectional"))
      (node (ref "U$22") (pin "3") (pinfunction "SCL_3") (pintype "bidirectional"))
      (node (ref "U$22") (pin "31") (pinfunction "R1+_31") (pintype "passive"))
      (node (ref "U$27") (pin "1") (pinfunction "S12_1") (pintype "bidirectional"))
    )
    (net (code "49") (name "Net-(U$23-ADDR2)") (class "Default")
      (node (ref "U$23") (pin "1") (pinfunction "SDA_1") (pintype "bidirectional"))
      (node (ref "U$23") (pin "15") (pinfunction "SDA2_15") (pintype "bidirectional"))
      (node (ref "U$23") (pin "19") (pinfunction "ADDR2_19") (pintype "bidirectional"))
      (node (ref "U$23") (pin "22") (pinfunction "SDA3_22") (pintype "bidirectional"))
      (node (ref "U$23") (pin "33") (pinfunction "R2+_33") (pintype "passive"))
      (node (ref "U$23") (pin "8") (pinfunction "SDA1_8") (pintype "bidirectional"))
      (node (ref "U$26") (pin "36") (pinfunction "S28_36") (pintype "bidirectional"))
    )
    (net (code "50") (name "Net-(U$23-ADDR3)") (class "Default")
      (node (ref "U$23") (pin "10") (pinfunction "SCL1_10") (pintype "bidirectional"))
      (node (ref "U$23") (pin "17") (pinfunction "SCL2_17") (pintype "bidirectional"))
      (node (ref "U$23") (pin "24") (pinfunction "SCL3_24") (pintype "bidirectional"))
      (node (ref "U$23") (pin "26") (pinfunction "ADDR3_26") (pintype "bidirectional"))
      (node (ref "U$23") (pin "3") (pinfunction "SCL_3") (pintype "bidirectional"))
      (node (ref "U$23") (pin "31") (pinfunction "R1+_31") (pintype "passive"))
      (node (ref "U$27") (pin "31") (pinfunction "S23_31") (pintype "bidirectional"))
    )
    (net (code "51") (name "Net-(U$24-ADDR2)") (class "Default")
      (node (ref "U$24") (pin "1") (pinfunction "SDA_1") (pintype "bidirectional"))
      (node (ref "U$24") (pin "15") (pinfunction "SDA2_15") (pintype "bidirectional"))
      (node (ref "U$24") (pin "19") (pinfunction "ADDR2_19") (pintype "bidirectional"))
      (node (ref "U$24") (pin "22") (pinfunction "SDA3_22") (pintype "bidirectional"))
      (node (ref "U$24") (pin "33") (pinfunction "R2+_33") (pintype "passive"))
      (node (ref "U$24") (pin "8") (pinfunction "SDA1_8") (pintype "bidirectional"))
      (node (ref "U$26") (pin "25") (pinfunction "S17_25") (pintype "bidirectional"))
    )
    (net (code "52") (name "Net-(U$24-ADDR3)") (class "Default")
      (node (ref "U$24") (pin "10") (pinfunction "SCL1_10") (pintype "bidirectional"))
      (node (ref "U$24") (pin "17") (pinfunction "SCL2_17") (pintype "bidirectional"))
      (node (ref "U$24") (pin "24") (pinfunction "SCL3_24") (pintype "bidirectional"))
      (node (ref "U$24") (pin "26") (pinfunction "ADDR3_26") (pintype "bidirectional"))
      (node (ref "U$24") (pin "3") (pinfunction "SCL_3") (pintype "bidirectional"))
      (node (ref "U$24") (pin "31") (pinfunction "R1+_31") (pintype "passive"))
      (node (ref "U$27") (pin "25") (pinfunction "S17_25") (pintype "bidirectional"))
    )
    (net (code "53") (name "Net-(U$26-S4)") (class "Default")
      (node (ref "U$26") (pin "9") (pinfunction "S4_9") (pintype "bidirectional"))
      (node (ref "U$9") (pin "1") (pinfunction "SDA_1") (pintype "bidirectional"))
      (node (ref "U$9") (pin "15") (pinfunction "SDA2_15") (pintype "bidirectional"))
      (node (ref "U$9") (pin "19") (pinfunction "ADDR2_19") (pintype "bidirectional"))
      (node (ref "U$9") (pin "22") (pinfunction "SDA3_22") (pintype "bidirectional"))
      (node (ref "U$9") (pin "33") (pinfunction "R2+_33") (pintype "passive"))
      (node (ref "U$9") (pin "8") (pinfunction "SDA1_8") (pintype "bidirectional"))
    )
    (net (code "54") (name "Net-(U$26-S5)") (class "Default")
      (node (ref "U$26") (pin "8") (pinfunction "S5_8") (pintype "bidirectional"))
      (node (ref "U$5") (pin "1") (pinfunction "SDA_1") (pintype "bidirectional"))
      (node (ref "U$5") (pin "15") (pinfunction "SDA2_15") (pintype "bidirectional"))
      (node (ref "U$5") (pin "19") (pinfunction "ADDR2_19") (pintype "bidirectional"))
      (node (ref "U$5") (pin "22") (pinfunction "SDA3_22") (pintype "bidirectional"))
      (node (ref "U$5") (pin "33") (pinfunction "R2+_33") (pintype "passive"))
      (node (ref "U$5") (pin "8") (pinfunction "SDA1_8") (pintype "bidirectional"))
    )
    (net (code "55") (name "Net-(U$26-S8)") (class "Default")
      (node (ref "U$26") (pin "5") (pinfunction "S8_5") (pintype "bidirectional"))
      (node (ref "U$6") (pin "1") (pinfunction "SDA_1") (pintype "bidirectional"))
      (node (ref "U$6") (pin "15") (pinfunction "SDA2_15") (pintype "bidirectional"))
      (node (ref "U$6") (pin "19") (pinfunction "ADDR2_19") (pintype "bidirectional"))
      (node (ref "U$6") (pin "22") (pinfunction "SDA3_22") (pintype "bidirectional"))
      (node (ref "U$6") (pin "33") (pinfunction "R2+_33") (pintype "passive"))
      (node (ref "U$6") (pin "8") (pinfunction "SDA1_8") (pintype "bidirectional"))
    )
    (net (code "56") (name "Net-(U$26-S21)") (class "Default")
      (node (ref "U$26") (pin "29") (pinfunction "S21_29") (pintype "bidirectional"))
      (node (ref "U$8") (pin "1") (pinfunction "SDA_1") (pintype "bidirectional"))
      (node (ref "U$8") (pin "15") (pinfunction "SDA2_15") (pintype "bidirectional"))
      (node (ref "U$8") (pin "19") (pinfunction "ADDR2_19") (pintype "bidirectional"))
      (node (ref "U$8") (pin "22") (pinfunction "SDA3_22") (pintype "bidirectional"))
      (node (ref "U$8") (pin "33") (pinfunction "R2+_33") (pintype "passive"))
      (node (ref "U$8") (pin "8") (pinfunction "SDA1_8") (pintype "bidirectional"))
    )
    (net (code "57") (name "Net-(U$26-S22)") (class "Default")
      (node (ref "U$26") (pin "30") (pinfunction "S22_30") (pintype "bidirectional"))
      (node (ref "U$4") (pin "1") (pinfunction "SDA_1") (pintype "bidirectional"))
      (node (ref "U$4") (pin "15") (pinfunction "SDA2_15") (pintype "bidirectional"))
      (node (ref "U$4") (pin "19") (pinfunction "ADDR2_19") (pintype "bidirectional"))
      (node (ref "U$4") (pin "22") (pinfunction "SDA3_22") (pintype "bidirectional"))
      (node (ref "U$4") (pin "33") (pinfunction "R2+_33") (pintype "passive"))
      (node (ref "U$4") (pin "8") (pinfunction "SDA1_8") (pintype "bidirectional"))
    )
    (net (code "58") (name "Net-(U$26-S23)") (class "Default")
      (node (ref "U$26") (pin "31") (pinfunction "S23_31") (pintype "bidirectional"))
      (node (ref "U$3") (pin "1") (pinfunction "SDA_1") (pintype "bidirectional"))
      (node (ref "U$3") (pin "15") (pinfunction "SDA2_15") (pintype "bidirectional"))
      (node (ref "U$3") (pin "19") (pinfunction "ADDR2_19") (pintype "bidirectional"))
      (node (ref "U$3") (pin "22") (pinfunction "SDA3_22") (pintype "bidirectional"))
      (node (ref "U$3") (pin "33") (pinfunction "R2+_33") (pintype "passive"))
      (node (ref "U$3") (pin "8") (pinfunction "SDA1_8") (pintype "bidirectional"))
    )
    (net (code "59") (name "Net-(U$26-S24)") (class "Default")
      (node (ref "U$26") (pin "32") (pinfunction "S24_32") (pintype "bidirectional"))
      (node (ref "U$7") (pin "1") (pinfunction "SDA_1") (pintype "bidirectional"))
      (node (ref "U$7") (pin "15") (pinfunction "SDA2_15") (pintype "bidirectional"))
      (node (ref "U$7") (pin "19") (pinfunction "ADDR2_19") (pintype "bidirectional"))
      (node (ref "U$7") (pin "22") (pinfunction "SDA3_22") (pintype "bidirectional"))
      (node (ref "U$7") (pin "33") (pinfunction "R2+_33") (pintype "passive"))
      (node (ref "U$7") (pin "8") (pinfunction "SDA1_8") (pintype "bidirectional"))
    )
    (net (code "60") (name "Net-(U$27-S2)") (class "Default")
      (node (ref "U$27") (pin "11") (pinfunction "S2_11") (pintype "bidirectional"))
      (node (ref "U$5") (pin "10") (pinfunction "SCL1_10") (pintype "bidirectional"))
      (node (ref "U$5") (pin "17") (pinfunction "SCL2_17") (pintype "bidirectional"))
      (node (ref "U$5") (pin "24") (pinfunction "SCL3_24") (pintype "bidirectional"))
      (node (ref "U$5") (pin "26") (pinfunction "ADDR3_26") (pintype "bidirectional"))
      (node (ref "U$5") (pin "3") (pinfunction "SCL_3") (pintype "bidirectional"))
      (node (ref "U$5") (pin "31") (pinfunction "R1+_31") (pintype "passive"))
    )
    (net (code "61") (name "Net-(U$27-S3)") (class "Default")
      (node (ref "U$27") (pin "10") (pinfunction "S3_10") (pintype "bidirectional"))
      (node (ref "U$9") (pin "10") (pinfunction "SCL1_10") (pintype "bidirectional"))
      (node (ref "U$9") (pin "17") (pinfunction "SCL2_17") (pintype "bidirectional"))
      (node (ref "U$9") (pin "24") (pinfunction "SCL3_24") (pintype "bidirectional"))
      (node (ref "U$9") (pin "26") (pinfunction "ADDR3_26") (pintype "bidirectional"))
      (node (ref "U$9") (pin "3") (pinfunction "SCL_3") (pintype "bidirectional"))
      (node (ref "U$9") (pin "31") (pinfunction "R1+_31") (pintype "passive"))
    )
    (net (code "62") (name "Net-(U$27-S8)") (class "Default")
      (node (ref "U$27") (pin "5") (pinfunction "S8_5") (pintype "bidirectional"))
      (node (ref "U$6") (pin "10") (pinfunction "SCL1_10") (pintype "bidirectional"))
      (node (ref "U$6") (pin "17") (pinfunction "SCL2_17") (pintype "bidirectional"))
      (node (ref "U$6") (pin "24") (pinfunction "SCL3_24") (pintype "bidirectional"))
      (node (ref "U$6") (pin "26") (pinfunction "ADDR3_26") (pintype "bidirectional"))
      (node (ref "U$6") (pin "3") (pinfunction "SCL_3") (pintype "bidirectional"))
      (node (ref "U$6") (pin "31") (pinfunction "R1+_31") (pintype "passive"))
    )
    (net (code "63") (name "Net-(U$27-S21)") (class "Default")
      (node (ref "U$27") (pin "29") (pinfunction "S21_29") (pintype "bidirectional"))
      (node (ref "U$8") (pin "10") (pinfunction "SCL1_10") (pintype "bidirectional"))
      (node (ref "U$8") (pin "17") (pinfunction "SCL2_17") (pintype "bidirectional"))
      (node (ref "U$8") (pin "24") (pinfunction "SCL3_24") (pintype "bidirectional"))
      (node (ref "U$8") (pin "26") (pinfunction "ADDR3_26") (pintype "bidirectional"))
      (node (ref "U$8") (pin "3") (pinfunction "SCL_3") (pintype "bidirectional"))
      (node (ref "U$8") (pin "31") (pinfunction "R1+_31") (pintype "passive"))
    )
    (net (code "64") (name "Net-(U$27-S22)") (class "Default")
      (node (ref "U$27") (pin "30") (pinfunction "S22_30") (pintype "bidirectional"))
      (node (ref "U$4") (pin "10") (pinfunction "SCL1_10") (pintype "bidirectional"))
      (node (ref "U$4") (pin "17") (pinfunction "SCL2_17") (pintype "bidirectional"))
      (node (ref "U$4") (pin "24") (pinfunction "SCL3_24") (pintype "bidirectional"))
      (node (ref "U$4") (pin "26") (pinfunction "ADDR3_26") (pintype "bidirectional"))
      (node (ref "U$4") (pin "3") (pinfunction "SCL_3") (pintype "bidirectional"))
      (node (ref "U$4") (pin "31") (pinfunction "R1+_31") (pintype "passive"))
    )
    (net (code "65") (name "Net-(U$27-S27)") (class "Default")
      (node (ref "U$27") (pin "35") (pinfunction "S27_35") (pintype "bidirectional"))
      (node (ref "U$7") (pin "10") (pinfunction "SCL1_10") (pintype "bidirectional"))
      (node (ref "U$7") (pin "17") (pinfunction "SCL2_17") (pintype "bidirectional"))
      (node (ref "U$7") (pin "24") (pinfunction "SCL3_24") (pintype "bidirectional"))
      (node (ref "U$7") (pin "26") (pinfunction "ADDR3_26") (pintype "bidirectional"))
      (node (ref "U$7") (pin "3") (pinfunction "SCL_3") (pintype "bidirectional"))
      (node (ref "U$7") (pin "31") (pinfunction "R1+_31") (pintype "passive"))
    )
    (net (code "66") (name "Net-(U$27-S28)") (class "Default")
      (node (ref "U$27") (pin "36") (pinfunction "S28_36") (pintype "bidirectional"))
      (node (ref "U$3") (pin "10") (pinfunction "SCL1_10") (pintype "bidirectional"))
      (node (ref "U$3") (pin "17") (pinfunction "SCL2_17") (pintype "bidirectional"))
      (node (ref "U$3") (pin "24") (pinfunction "SCL3_24") (pintype "bidirectional"))
      (node (ref "U$3") (pin "26") (pinfunction "ADDR3_26") (pintype "bidirectional"))
      (node (ref "U$3") (pin "3") (pinfunction "SCL_3") (pintype "bidirectional"))
      (node (ref "U$3") (pin "31") (pinfunction "R1+_31") (pintype "passive"))
    )
    (net (code "67") (name "VDD") (class "Default")
      (node (ref "C1") (pin "2") (pinfunction "2_2") (pintype "passive"))
      (node (ref "C2") (pin "2") (pinfunction "2_2") (pintype "passive"))
      (node (ref "JP2") (pin "2") (pinfunction "2_2") (pintype "passive"))
      (node (ref "JP3") (pin "2") (pinfunction "2_2") (pintype "passive"))
      (node (ref "R1") (pin "2") (pinfunction "2_2") (pintype "passive"))
      (node (ref "R2") (pin "2") (pinfunction "2_2") (pintype "passive"))
      (node (ref "U$1") (pin "12") (pinfunction "ADDR1_12") (pintype "bidirectional"))
      (node (ref "U$1") (pin "13") (pinfunction "VDD1_13") (pintype "bidirectional"))
      (node (ref "U$1") (pin "20") (pinfunction "VDD2_20") (pintype "bidirectional"))
      (node (ref "U$1") (pin "27") (pinfunction "VDD3_27") (pintype "bidirectional"))
      (node (ref "U$1") (pin "29") (pinfunction "C+_29") (pintype "passive"))
      (node (ref "U$1") (pin "32") (pinfunction "GND_32") (pintype "passive"))
      (node (ref "U$1") (pin "34") (pinfunction "GND_34") (pintype "passive"))
      (node (ref "U$1") (pin "6") (pinfunction "VDD_6") (pintype "bidirectional"))
      (node (ref "U$10") (pin "12") (pinfunction "ADDR1_12") (pintype "bidirectional"))
      (node (ref "U$10") (pin "13") (pinfunction "VDD1_13") (pintype "bidirectional"))
      (node (ref "U$10") (pin "20") (pinfunction "VDD2_20") (pintype "bidirectional"))
      (node (ref "U$10") (pin "27") (pinfunction "VDD3_27") (pintype "bidirectional"))
      (node (ref "U$10") (pin "29") (pinfunction "C+_29") (pintype "passive"))
      (node (ref "U$10") (pin "32") (pinfunction "GND_32") (pintype "passive"))
      (node (ref "U$10") (pin "34") (pinfunction "GND_34") (pintype "passive"))
      (node (ref "U$10") (pin "6") (pinfunction "VDD_6") (pintype "bidirectional"))
      (node (ref "U$11") (pin "12") (pinfunction "ADDR1_12") (pintype "bidirectional"))
      (node (ref "U$11") (pin "13") (pinfunction "VDD1_13") (pintype "bidirectional"))
      (node (ref "U$11") (pin "20") (pinfunction "VDD2_20") (pintype "bidirectional"))
      (node (ref "U$11") (pin "27") (pinfunction "VDD3_27") (pintype "bidirectional"))
      (node (ref "U$11") (pin "29") (pinfunction "C+_29") (pintype "passive"))
      (node (ref "U$11") (pin "32") (pinfunction "GND_32") (pintype "passive"))
      (node (ref "U$11") (pin "34") (pinfunction "GND_34") (pintype "passive"))
      (node (ref "U$11") (pin "6") (pinfunction "VDD_6") (pintype "bidirectional"))
      (node (ref "U$12") (pin "12") (pinfunction "ADDR1_12") (pintype "bidirectional"))
      (node (ref "U$12") (pin "13") (pinfunction "VDD1_13") (pintype "bidirectional"))
      (node (ref "U$12") (pin "20") (pinfunction "VDD2_20") (pintype "bidirectional"))
      (node (ref "U$12") (pin "27") (pinfunction "VDD3_27") (pintype "bidirectional"))
      (node (ref "U$12") (pin "29") (pinfunction "C+_29") (pintype "passive"))
      (node (ref "U$12") (pin "32") (pinfunction "GND_32") (pintype "passive"))
      (node (ref "U$12") (pin "34") (pinfunction "GND_34") (pintype "passive"))
      (node (ref "U$12") (pin "6") (pinfunction "VDD_6") (pintype "bidirectional"))
      (node (ref "U$13") (pin "12") (pinfunction "ADDR1_12") (pintype "bidirectional"))
      (node (ref "U$13") (pin "13") (pinfunction "VDD1_13") (pintype "bidirectional"))
      (node (ref "U$13") (pin "20") (pinfunction "VDD2_20") (pintype "bidirectional"))
      (node (ref "U$13") (pin "27") (pinfunction "VDD3_27") (pintype "bidirectional"))
      (node (ref "U$13") (pin "29") (pinfunction "C+_29") (pintype "passive"))
      (node (ref "U$13") (pin "32") (pinfunction "GND_32") (pintype "passive"))
      (node (ref "U$13") (pin "34") (pinfunction "GND_34") (pintype "passive"))
      (node (ref "U$13") (pin "6") (pinfunction "VDD_6") (pintype "bidirectional"))
      (node (ref "U$14") (pin "12") (pinfunction "ADDR1_12") (pintype "bidirectional"))
      (node (ref "U$14") (pin "13") (pinfunction "VDD1_13") (pintype "bidirectional"))
      (node (ref "U$14") (pin "20") (pinfunction "VDD2_20") (pintype "bidirectional"))
      (node (ref "U$14") (pin "27") (pinfunction "VDD3_27") (pintype "bidirectional"))
      (node (ref "U$14") (pin "29") (pinfunction "C+_29") (pintype "passive"))
      (node (ref "U$14") (pin "32") (pinfunction "GND_32") (pintype "passive"))
      (node (ref "U$14") (pin "34") (pinfunction "GND_34") (pintype "passive"))
      (node (ref "U$14") (pin "6") (pinfunction "VDD_6") (pintype "bidirectional"))
      (node (ref "U$15") (pin "12") (pinfunction "ADDR1_12") (pintype "bidirectional"))
      (node (ref "U$15") (pin "13") (pinfunction "VDD1_13") (pintype "bidirectional"))
      (node (ref "U$15") (pin "20") (pinfunction "VDD2_20") (pintype "bidirectional"))
      (node (ref "U$15") (pin "27") (pinfunction "VDD3_27") (pintype "bidirectional"))
      (node (ref "U$15") (pin "29") (pinfunction "C+_29") (pintype "passive"))
      (node (ref "U$15") (pin "32") (pinfunction "GND_32") (pintype "passive"))
      (node (ref "U$15") (pin "34") (pinfunction "GND_34") (pintype "passive"))
      (node (ref "U$15") (pin "6") (pinfunction "VDD_6") (pintype "bidirectional"))
      (node (ref "U$16") (pin "12") (pinfunction "ADDR1_12") (pintype "bidirectional"))
      (node (ref "U$16") (pin "13") (pinfunction "VDD1_13") (pintype "bidirectional"))
      (node (ref "U$16") (pin "20") (pinfunction "VDD2_20") (pintype "bidirectional"))
      (node (ref "U$16") (pin "27") (pinfunction "VDD3_27") (pintype "bidirectional"))
      (node (ref "U$16") (pin "29") (pinfunction "C+_29") (pintype "passive"))
      (node (ref "U$16") (pin "32") (pinfunction "GND_32") (pintype "passive"))
      (node (ref "U$16") (pin "34") (pinfunction "GND_34") (pintype "passive"))
      (node (ref "U$16") (pin "6") (pinfunction "VDD_6") (pintype "bidirectional"))
      (node (ref "U$17") (pin "12") (pinfunction "ADDR1_12") (pintype "bidirectional"))
      (node (ref "U$17") (pin "13") (pinfunction "VDD1_13") (pintype "bidirectional"))
      (node (ref "U$17") (pin "20") (pinfunction "VDD2_20") (pintype "bidirectional"))
      (node (ref "U$17") (pin "27") (pinfunction "VDD3_27") (pintype "bidirectional"))
      (node (ref "U$17") (pin "29") (pinfunction "C+_29") (pintype "passive"))
      (node (ref "U$17") (pin "32") (pinfunction "GND_32") (pintype "passive"))
      (node (ref "U$17") (pin "34") (pinfunction "GND_34") (pintype "passive"))
      (node (ref "U$17") (pin "6") (pinfunction "VDD_6") (pintype "bidirectional"))
      (node (ref "U$18") (pin "12") (pinfunction "ADDR1_12") (pintype "bidirectional"))
      (node (ref "U$18") (pin "13") (pinfunction "VDD1_13") (pintype "bidirectional"))
      (node (ref "U$18") (pin "20") (pinfunction "VDD2_20") (pintype "bidirectional"))
      (node (ref "U$18") (pin "27") (pinfunction "VDD3_27") (pintype "bidirectional"))
      (node (ref "U$18") (pin "29") (pinfunction "C+_29") (pintype "passive"))
      (node (ref "U$18") (pin "32") (pinfunction "GND_32") (pintype "passive"))
      (node (ref "U$18") (pin "34") (pinfunction "GND_34") (pintype "passive"))
      (node (ref "U$18") (pin "6") (pinfunction "VDD_6") (pintype "bidirectional"))
      (node (ref "U$19") (pin "12") (pinfunction "ADDR1_12") (pintype "bidirectional"))
      (node (ref "U$19") (pin "13") (pinfunction "VDD1_13") (pintype "bidirectional"))
      (node (ref "U$19") (pin "20") (pinfunction "VDD2_20") (pintype "bidirectional"))
      (node (ref "U$19") (pin "27") (pinfunction "VDD3_27") (pintype "bidirectional"))
      (node (ref "U$19") (pin "29") (pinfunction "C+_29") (pintype "passive"))
      (node (ref "U$19") (pin "32") (pinfunction "GND_32") (pintype "passive"))
      (node (ref "U$19") (pin "34") (pinfunction "GND_34") (pintype "passive"))
      (node (ref "U$19") (pin "6") (pinfunction "VDD_6") (pintype "bidirectional"))
      (node (ref "U$2") (pin "12") (pinfunction "ADDR1_12") (pintype "bidirectional"))
      (node (ref "U$2") (pin "13") (pinfunction "VDD1_13") (pintype "bidirectional"))
      (node (ref "U$2") (pin "20") (pinfunction "VDD2_20") (pintype "bidirectional"))
      (node (ref "U$2") (pin "27") (pinfunction "VDD3_27") (pintype "bidirectional"))
      (node (ref "U$2") (pin "29") (pinfunction "C+_29") (pintype "passive"))
      (node (ref "U$2") (pin "32") (pinfunction "GND_32") (pintype "passive"))
      (node (ref "U$2") (pin "34") (pinfunction "GND_34") (pintype "passive"))
      (node (ref "U$2") (pin "6") (pinfunction "VDD_6") (pintype "bidirectional"))
      (node (ref "U$20") (pin "12") (pinfunction "ADDR1_12") (pintype "bidirectional"))
      (node (ref "U$20") (pin "13") (pinfunction "VDD1_13") (pintype "bidirectional"))
      (node (ref "U$20") (pin "20") (pinfunction "VDD2_20") (pintype "bidirectional"))
      (node (ref "U$20") (pin "27") (pinfunction "VDD3_27") (pintype "bidirectional"))
      (node (ref "U$20") (pin "29") (pinfunction "C+_29") (pintype "passive"))
      (node (ref "U$20") (pin "32") (pinfunction "GND_32") (pintype "passive"))
      (node (ref "U$20") (pin "34") (pinfunction "GND_34") (pintype "passive"))
      (node (ref "U$20") (pin "6") (pinfunction "VDD_6") (pintype "bidirectional"))
      (node (ref "U$21") (pin "12") (pinfunction "ADDR1_12") (pintype "bidirectional"))
      (node (ref "U$21") (pin "13") (pinfunction "VDD1_13") (pintype "bidirectional"))
      (node (ref "U$21") (pin "20") (pinfunction "VDD2_20") (pintype "bidirectional"))
      (node (ref "U$21") (pin "27") (pinfunction "VDD3_27") (pintype "bidirectional"))
      (node (ref "U$21") (pin "29") (pinfunction "C+_29") (pintype "passive"))
      (node (ref "U$21") (pin "32") (pinfunction "GND_32") (pintype "passive"))
      (node (ref "U$21") (pin "34") (pinfunction "GND_34") (pintype "passive"))
      (node (ref "U$21") (pin "6") (pinfunction "VDD_6") (pintype "bidirectional"))
      (node (ref "U$22") (pin "12") (pinfunction "ADDR1_12") (pintype "bidirectional"))
      (node (ref "U$22") (pin "13") (pinfunction "VDD1_13") (pintype "bidirectional"))
      (node (ref "U$22") (pin "20") (pinfunction "VDD2_20") (pintype "bidirectional"))
      (node (ref "U$22") (pin "27") (pinfunction "VDD3_27") (pintype "bidirectional"))
      (node (ref "U$22") (pin "29") (pinfunction "C+_29") (pintype "passive"))
      (node (ref "U$22") (pin "32") (pinfunction "GND_32") (pintype "passive"))
      (node (ref "U$22") (pin "34") (pinfunction "GND_34") (pintype "passive"))
      (node (ref "U$22") (pin "6") (pinfunction "VDD_6") (pintype "bidirectional"))
      (node (ref "U$23") (pin "12") (pinfunction "ADDR1_12") (pintype "bidirectional"))
      (node (ref "U$23") (pin "13") (pinfunction "VDD1_13") (pintype "bidirectional"))
      (node (ref "U$23") (pin "20") (pinfunction "VDD2_20") (pintype "bidirectional"))
      (node (ref "U$23") (pin "27") (pinfunction "VDD3_27") (pintype "bidirectional"))
      (node (ref "U$23") (pin "29") (pinfunction "C+_29") (pintype "passive"))
      (node (ref "U$23") (pin "32") (pinfunction "GND_32") (pintype "passive"))
      (node (ref "U$23") (pin "34") (pinfunction "GND_34") (pintype "passive"))
      (node (ref "U$23") (pin "6") (pinfunction "VDD_6") (pintype "bidirectional"))
      (node (ref "U$24") (pin "12") (pinfunction "ADDR1_12") (pintype "bidirectional"))
      (node (ref "U$24") (pin "13") (pinfunction "VDD1_13") (pintype "bidirectional"))
      (node (ref "U$24") (pin "20") (pinfunction "VDD2_20") (pintype "bidirectional"))
      (node (ref "U$24") (pin "27") (pinfunction "VDD3_27") (pintype "bidirectional"))
      (node (ref "U$24") (pin "29") (pinfunction "C+_29") (pintype "passive"))
      (node (ref "U$24") (pin "32") (pinfunction "GND_32") (pintype "passive"))
      (node (ref "U$24") (pin "34") (pinfunction "GND_34") (pintype "passive"))
      (node (ref "U$24") (pin "6") (pinfunction "VDD_6") (pintype "bidirectional"))
      (node (ref "U$25") (pin "1") (pinfunction "P$1_1") (pintype "bidirectional"))
      (node (ref "U$26") (pin "13") (pinfunction "VDD_13") (pintype "bidirectional"))
      (node (ref "U$26") (pin "14") (pinfunction "VDD_14") (pintype "bidirectional"))
      (node (ref "U$27") (pin "13") (pinfunction "VDD_13") (pintype "bidirectional"))
      (node (ref "U$27") (pin "14") (pinfunction "VDD_14") (pintype "bidirectional"))
      (node (ref "U$28") (pin "2") (pinfunction "P$2_2") (pintype "bidirectional"))
      (node (ref "U$29") (pin "VDD") (pinfunction "P$3_VDD") (pintype "bidirectional"))
      (node (ref "U$3") (pin "12") (pinfunction "ADDR1_12") (pintype "bidirectional"))
      (node (ref "U$3") (pin "13") (pinfunction "VDD1_13") (pintype "bidirectional"))
      (node (ref "U$3") (pin "20") (pinfunction "VDD2_20") (pintype "bidirectional"))
      (node (ref "U$3") (pin "27") (pinfunction "VDD3_27") (pintype "bidirectional"))
      (node (ref "U$3") (pin "29") (pinfunction "C+_29") (pintype "passive"))
      (node (ref "U$3") (pin "32") (pinfunction "GND_32") (pintype "passive"))
      (node (ref "U$3") (pin "34") (pinfunction "GND_34") (pintype "passive"))
      (node (ref "U$3") (pin "6") (pinfunction "VDD_6") (pintype "bidirectional"))
      (node (ref "U$4") (pin "12") (pinfunction "ADDR1_12") (pintype "bidirectional"))
      (node (ref "U$4") (pin "13") (pinfunction "VDD1_13") (pintype "bidirectional"))
      (node (ref "U$4") (pin "20") (pinfunction "VDD2_20") (pintype "bidirectional"))
      (node (ref "U$4") (pin "27") (pinfunction "VDD3_27") (pintype "bidirectional"))
      (node (ref "U$4") (pin "29") (pinfunction "C+_29") (pintype "passive"))
      (node (ref "U$4") (pin "32") (pinfunction "GND_32") (pintype "passive"))
      (node (ref "U$4") (pin "34") (pinfunction "GND_34") (pintype "passive"))
      (node (ref "U$4") (pin "6") (pinfunction "VDD_6") (pintype "bidirectional"))
      (node (ref "U$5") (pin "12") (pinfunction "ADDR1_12") (pintype "bidirectional"))
      (node (ref "U$5") (pin "13") (pinfunction "VDD1_13") (pintype "bidirectional"))
      (node (ref "U$5") (pin "20") (pinfunction "VDD2_20") (pintype "bidirectional"))
      (node (ref "U$5") (pin "27") (pinfunction "VDD3_27") (pintype "bidirectional"))
      (node (ref "U$5") (pin "29") (pinfunction "C+_29") (pintype "passive"))
      (node (ref "U$5") (pin "32") (pinfunction "GND_32") (pintype "passive"))
      (node (ref "U$5") (pin "34") (pinfunction "GND_34") (pintype "passive"))
      (node (ref "U$5") (pin "6") (pinfunction "VDD_6") (pintype "bidirectional"))
      (node (ref "U$6") (pin "12") (pinfunction "ADDR1_12") (pintype "bidirectional"))
      (node (ref "U$6") (pin "13") (pinfunction "VDD1_13") (pintype "bidirectional"))
      (node (ref "U$6") (pin "20") (pinfunction "VDD2_20") (pintype "bidirectional"))
      (node (ref "U$6") (pin "27") (pinfunction "VDD3_27") (pintype "bidirectional"))
      (node (ref "U$6") (pin "29") (pinfunction "C+_29") (pintype "passive"))
      (node (ref "U$6") (pin "32") (pinfunction "GND_32") (pintype "passive"))
      (node (ref "U$6") (pin "34") (pinfunction "GND_34") (pintype "passive"))
      (node (ref "U$6") (pin "6") (pinfunction "VDD_6") (pintype "bidirectional"))
      (node (ref "U$7") (pin "12") (pinfunction "ADDR1_12") (pintype "bidirectional"))
      (node (ref "U$7") (pin "13") (pinfunction "VDD1_13") (pintype "bidirectional"))
      (node (ref "U$7") (pin "20") (pinfunction "VDD2_20") (pintype "bidirectional"))
      (node (ref "U$7") (pin "27") (pinfunction "VDD3_27") (pintype "bidirectional"))
      (node (ref "U$7") (pin "29") (pinfunction "C+_29") (pintype "passive"))
      (node (ref "U$7") (pin "32") (pinfunction "GND_32") (pintype "passive"))
      (node (ref "U$7") (pin "34") (pinfunction "GND_34") (pintype "passive"))
      (node (ref "U$7") (pin "6") (pinfunction "VDD_6") (pintype "bidirectional"))
      (node (ref "U$8") (pin "12") (pinfunction "ADDR1_12") (pintype "bidirectional"))
      (node (ref "U$8") (pin "13") (pinfunction "VDD1_13") (pintype "bidirectional"))
      (node (ref "U$8") (pin "20") (pinfunction "VDD2_20") (pintype "bidirectional"))
      (node (ref "U$8") (pin "27") (pinfunction "VDD3_27") (pintype "bidirectional"))
      (node (ref "U$8") (pin "29") (pinfunction "C+_29") (pintype "passive"))
      (node (ref "U$8") (pin "32") (pinfunction "GND_32") (pintype "passive"))
      (node (ref "U$8") (pin "34") (pinfunction "GND_34") (pintype "passive"))
      (node (ref "U$8") (pin "6") (pinfunction "VDD_6") (pintype "bidirectional"))
      (node (ref "U$9") (pin "12") (pinfunction "ADDR1_12") (pintype "bidirectional"))
      (node (ref "U$9") (pin "13") (pinfunction "VDD1_13") (pintype "bidirectional"))
      (node (ref "U$9") (pin "20") (pinfunction "VDD2_20") (pintype "bidirectional"))
      (node (ref "U$9") (pin "27") (pinfunction "VDD3_27") (pintype "bidirectional"))
      (node (ref "U$9") (pin "29") (pinfunction "C+_29") (pintype "passive"))
      (node (ref "U$9") (pin "32") (pinfunction "GND_32") (pintype "passive"))
      (node (ref "U$9") (pin "34") (pinfunction "GND_34") (pintype "passive"))
      (node (ref "U$9") (pin "6") (pinfunction "VDD_6") (pintype "bidirectional"))
    )
    (net (code "68") (name "unconnected-(JP1-Pad1)") (class "Default")
      (node (ref "JP1") (pin "1") (pinfunction "1_1") (pintype "passive"))
    )
    (net (code "69") (name "unconnected-(JP1-Pad2)") (class "Default")
      (node (ref "JP1") (pin "2") (pinfunction "2_2") (pintype "passive"))
    )
    (net (code "70") (name "unconnected-(JP1-Pad3)") (class "Default")
      (node (ref "JP1") (pin "3") (pinfunction "3_3") (pintype "passive"))
    )
    (net (code "71") (name "unconnected-(JP1-Pad4)") (class "Default")
      (node (ref "JP1") (pin "4") (pinfunction "4_4") (pintype "passive"))
    )
    (net (code "72") (name "unconnected-(JP1-Pad8)") (class "Default")
      (node (ref "JP1") (pin "8") (pinfunction "8_8") (pintype "passive"))
    )
    (net (code "73") (name "unconnected-(JP2-Pad1)") (class "Default")
      (node (ref "JP2") (pin "1") (pinfunction "1_1") (pintype "passive"))
    )
    (net (code "74") (name "unconnected-(JP2-Pad3)") (class "Default")
      (node (ref "JP2") (pin "3") (pinfunction "3_3") (pintype "passive"))
    )
    (net (code "75") (name "unconnected-(JP2-Pad13)") (class "Default")
      (node (ref "JP2") (pin "13") (pinfunction "13_13") (pintype "passive"))
    )
    (net (code "76") (name "unconnected-(JP3-Pad1)") (class "Default")
      (node (ref "JP3") (pin "1") (pinfunction "1_1") (pintype "passive"))
    )
    (net (code "77") (name "unconnected-(JP3-Pad3)") (class "Default")
      (node (ref "JP3") (pin "3") (pinfunction "3_3") (pintype "passive"))
    )
    (net (code "78") (name "unconnected-(JP3-Pad5)") (class "Default")
      (node (ref "JP3") (pin "5") (pinfunction "5_5") (pintype "passive"))
    )
    (net (code "79") (name "unconnected-(JP3-Pad6)") (class "Default")
      (node (ref "JP3") (pin "6") (pinfunction "6_6") (pintype "passive"))
    )
    (net (code "80") (name "unconnected-(JP3-Pad7)") (class "Default")
      (node (ref "JP3") (pin "7") (pinfunction "7_7") (pintype "passive"))
    )
    (net (code "81") (name "unconnected-(JP3-Pad8)") (class "Default")
      (node (ref "JP3") (pin "8") (pinfunction "8_8") (pintype "passive"))
    )
    (net (code "82") (name "unconnected-(JP3-Pad9)") (class "Default")
      (node (ref "JP3") (pin "9") (pinfunction "9_9") (pintype "passive"))
    )
    (net (code "83") (name "unconnected-(JP3-Pad10)") (class "Default")
      (node (ref "JP3") (pin "10") (pinfunction "10_10") (pintype "passive"))
    )
    (net (code "84") (name "unconnected-(JP3-Pad11)") (class "Default")
      (node (ref "JP3") (pin "11") (pinfunction "11_11") (pintype "passive"))
    )
    (net (code "85") (name "unconnected-(JP3-Pad12)") (class "Default")
      (node (ref "JP3") (pin "12") (pinfunction "12_12") (pintype "passive"))
    )
    (net (code "86") (name "unconnected-(JP3-Pad13)") (class "Default")
      (node (ref "JP3") (pin "13") (pinfunction "13_13") (pintype "passive"))
    )
    (net (code "87") (name "unconnected-(JP3-Pad14)") (class "Default")
      (node (ref "JP3") (pin "14") (pinfunction "14_14") (pintype "passive"))
    )
    (net (code "88") (name "unconnected-(JP3-Pad15)") (class "Default")
      (node (ref "JP3") (pin "15") (pinfunction "15_15") (pintype "passive"))
    )
    (net (code "89") (name "unconnected-(JP3-Pad16)") (class "Default")
      (node (ref "JP3") (pin "16") (pinfunction "16_16") (pintype "passive"))
    )
    (net (code "90") (name "unconnected-(JP4-Pad1)") (class "Default")
      (node (ref "JP4") (pin "1") (pinfunction "1_1") (pintype "passive"))
    )
    (net (code "91") (name "unconnected-(JP4-Pad2)") (class "Default")
      (node (ref "JP4") (pin "2") (pinfunction "2_2") (pintype "passive"))
    )
    (net (code "92") (name "unconnected-(JP4-Pad3)") (class "Default")
      (node (ref "JP4") (pin "3") (pinfunction "3_3") (pintype "passive"))
    )
    (net (code "93") (name "unconnected-(JP4-Pad4)") (class "Default")
      (node (ref "JP4") (pin "4") (pinfunction "4_4") (pintype "passive"))
    )
    (net (code "94") (name "unconnected-(JP4-Pad5)") (class "Default")
      (node (ref "JP4") (pin "5") (pinfunction "5_5") (pintype "passive"))
    )
    (net (code "95") (name "unconnected-(JP4-Pad6)") (class "Default")
      (node (ref "JP4") (pin "6") (pinfunction "6_6") (pintype "passive"))
    )
    (net (code "96") (name "unconnected-(JP4-Pad7)") (class "Default")
      (node (ref "JP4") (pin "7") (pinfunction "7_7") (pintype "passive"))
    )
    (net (code "97") (name "unconnected-(U$1-INT-Pad2)") (class "Default")
      (node (ref "U$1") (pin "2") (pinfunction "INT_2") (pintype "bidirectional"))
    )
    (net (code "98") (name "unconnected-(U$1-INT1-Pad9)") (class "Default")
      (node (ref "U$1") (pin "9") (pinfunction "INT1_9") (pintype "bidirectional"))
    )
    (net (code "99") (name "unconnected-(U$1-INT2-Pad16)") (class "Default")
      (node (ref "U$1") (pin "16") (pinfunction "INT2_16") (pintype "bidirectional"))
    )
    (net (code "100") (name "unconnected-(U$1-INT3-Pad23)") (class "Default")
      (node (ref "U$1") (pin "23") (pinfunction "INT3_23") (pintype "bidirectional"))
    )
    (net (code "101") (name "unconnected-(U$2-INT-Pad2)") (class "Default")
      (node (ref "U$2") (pin "2") (pinfunction "INT_2") (pintype "bidirectional"))
    )
    (net (code "102") (name "unconnected-(U$2-INT1-Pad9)") (class "Default")
      (node (ref "U$2") (pin "9") (pinfunction "INT1_9") (pintype "bidirectional"))
    )
    (net (code "103") (name "unconnected-(U$2-INT2-Pad16)") (class "Default")
      (node (ref "U$2") (pin "16") (pinfunction "INT2_16") (pintype "bidirectional"))
    )
    (net (code "104") (name "unconnected-(U$2-INT3-Pad23)") (class "Default")
      (node (ref "U$2") (pin "23") (pinfunction "INT3_23") (pintype "bidirectional"))
    )
    (net (code "105") (name "unconnected-(U$3-INT-Pad2)") (class "Default")
      (node (ref "U$3") (pin "2") (pinfunction "INT_2") (pintype "bidirectional"))
    )
    (net (code "106") (name "unconnected-(U$3-INT1-Pad9)") (class "Default")
      (node (ref "U$3") (pin "9") (pinfunction "INT1_9") (pintype "bidirectional"))
    )
    (net (code "107") (name "unconnected-(U$3-INT2-Pad16)") (class "Default")
      (node (ref "U$3") (pin "16") (pinfunction "INT2_16") (pintype "bidirectional"))
    )
    (net (code "108") (name "unconnected-(U$3-INT3-Pad23)") (class "Default")
      (node (ref "U$3") (pin "23") (pinfunction "INT3_23") (pintype "bidirectional"))
    )
    (net (code "109") (name "unconnected-(U$4-INT-Pad2)") (class "Default")
      (node (ref "U$4") (pin "2") (pinfunction "INT_2") (pintype "bidirectional"))
    )
    (net (code "110") (name "unconnected-(U$4-INT1-Pad9)") (class "Default")
      (node (ref "U$4") (pin "9") (pinfunction "INT1_9") (pintype "bidirectional"))
    )
    (net (code "111") (name "unconnected-(U$4-INT2-Pad16)") (class "Default")
      (node (ref "U$4") (pin "16") (pinfunction "INT2_16") (pintype "bidirectional"))
    )
    (net (code "112") (name "unconnected-(U$4-INT3-Pad23)") (class "Default")
      (node (ref "U$4") (pin "23") (pinfunction "INT3_23") (pintype "bidirectional"))
    )
    (net (code "113") (name "unconnected-(U$5-INT-Pad2)") (class "Default")
      (node (ref "U$5") (pin "2") (pinfunction "INT_2") (pintype "bidirectional"))
    )
    (net (code "114") (name "unconnected-(U$5-INT1-Pad9)") (class "Default")
      (node (ref "U$5") (pin "9") (pinfunction "INT1_9") (pintype "bidirectional"))
    )
    (net (code "115") (name "unconnected-(U$5-INT2-Pad16)") (class "Default")
      (node (ref "U$5") (pin "16") (pinfunction "INT2_16") (pintype "bidirectional"))
    )
    (net (code "116") (name "unconnected-(U$5-INT3-Pad23)") (class "Default")
      (node (ref "U$5") (pin "23") (pinfunction "INT3_23") (pintype "bidirectional"))
    )
    (net (code "117") (name "unconnected-(U$6-INT-Pad2)") (class "Default")
      (node (ref "U$6") (pin "2") (pinfunction "INT_2") (pintype "bidirectional"))
    )
    (net (code "118") (name "unconnected-(U$6-INT1-Pad9)") (class "Default")
      (node (ref "U$6") (pin "9") (pinfunction "INT1_9") (pintype "bidirectional"))
    )
    (net (code "119") (name "unconnected-(U$6-INT2-Pad16)") (class "Default")
      (node (ref "U$6") (pin "16") (pinfunction "INT2_16") (pintype "bidirectional"))
    )
    (net (code "120") (name "unconnected-(U$6-INT3-Pad23)") (class "Default")
      (node (ref "U$6") (pin "23") (pinfunction "INT3_23") (pintype "bidirectional"))
    )
    (net (code "121") (name "unconnected-(U$7-INT-Pad2)") (class "Default")
      (node (ref "U$7") (pin "2") (pinfunction "INT_2") (pintype "bidirectional"))
    )
    (net (code "122") (name "unconnected-(U$7-INT1-Pad9)") (class "Default")
      (node (ref "U$7") (pin "9") (pinfunction "INT1_9") (pintype "bidirectional"))
    )
    (net (code "123") (name "unconnected-(U$7-INT2-Pad16)") (class "Default")
      (node (ref "U$7") (pin "16") (pinfunction "INT2_16") (pintype "bidirectional"))
    )
    (net (code "124") (name "unconnected-(U$7-INT3-Pad23)") (class "Default")
      (node (ref "U$7") (pin "23") (pinfunction "INT3_23") (pintype "bidirectional"))
    )
    (net (code "125") (name "unconnected-(U$8-INT-Pad2)") (class "Default")
      (node (ref "U$8") (pin "2") (pinfunction "INT_2") (pintype "bidirectional"))
    )
    (net (code "126") (name "unconnected-(U$8-INT1-Pad9)") (class "Default")
      (node (ref "U$8") (pin "9") (pinfunction "INT1_9") (pintype "bidirectional"))
    )
    (net (code "127") (name "unconnected-(U$8-INT2-Pad16)") (class "Default")
      (node (ref "U$8") (pin "16") (pinfunction "INT2_16") (pintype "bidirectional"))
    )
    (net (code "128") (name "unconnected-(U$8-INT3-Pad23)") (class "Default")
      (node (ref "U$8") (pin "23") (pinfunction "INT3_23") (pintype "bidirectional"))
    )
    (net (code "129") (name "unconnected-(U$9-INT-Pad2)") (class "Default")
      (node (ref "U$9") (pin "2") (pinfunction "INT_2") (pintype "bidirectional"))
    )
    (net (code "130") (name "unconnected-(U$9-INT1-Pad9)") (class "Default")
      (node (ref "U$9") (pin "9") (pinfunction "INT1_9") (pintype "bidirectional"))
    )
    (net (code "131") (name "unconnected-(U$9-INT2-Pad16)") (class "Default")
      (node (ref "U$9") (pin "16") (pinfunction "INT2_16") (pintype "bidirectional"))
    )
    (net (code "132") (name "unconnected-(U$9-INT3-Pad23)") (class "Default")
      (node (ref "U$9") (pin "23") (pinfunction "INT3_23") (pintype "bidirectional"))
    )
    (net (code "133") (name "unconnected-(U$10-INT-Pad2)") (class "Default")
      (node (ref "U$10") (pin "2") (pinfunction "INT_2") (pintype "bidirectional"))
    )
    (net (code "134") (name "unconnected-(U$10-INT1-Pad9)") (class "Default")
      (node (ref "U$10") (pin "9") (pinfunction "INT1_9") (pintype "bidirectional"))
    )
    (net (code "135") (name "unconnected-(U$10-INT2-Pad16)") (class "Default")
      (node (ref "U$10") (pin "16") (pinfunction "INT2_16") (pintype "bidirectional"))
    )
    (net (code "136") (name "unconnected-(U$10-INT3-Pad23)") (class "Default")
      (node (ref "U$10") (pin "23") (pinfunction "INT3_23") (pintype "bidirectional"))
    )
    (net (code "137") (name "unconnected-(U$11-INT-Pad2)") (class "Default")
      (node (ref "U$11") (pin "2") (pinfunction "INT_2") (pintype "bidirectional"))
    )
    (net (code "138") (name "unconnected-(U$11-INT1-Pad9)") (class "Default")
      (node (ref "U$11") (pin "9") (pinfunction "INT1_9") (pintype "bidirectional"))
    )
    (net (code "139") (name "unconnected-(U$11-INT2-Pad16)") (class "Default")
      (node (ref "U$11") (pin "16") (pinfunction "INT2_16") (pintype "bidirectional"))
    )
    (net (code "140") (name "unconnected-(U$11-INT3-Pad23)") (class "Default")
      (node (ref "U$11") (pin "23") (pinfunction "INT3_23") (pintype "bidirectional"))
    )
    (net (code "141") (name "unconnected-(U$12-INT-Pad2)") (class "Default")
      (node (ref "U$12") (pin "2") (pinfunction "INT_2") (pintype "bidirectional"))
    )
    (net (code "142") (name "unconnected-(U$12-INT1-Pad9)") (class "Default")
      (node (ref "U$12") (pin "9") (pinfunction "INT1_9") (pintype "bidirectional"))
    )
    (net (code "143") (name "unconnected-(U$12-INT2-Pad16)") (class "Default")
      (node (ref "U$12") (pin "16") (pinfunction "INT2_16") (pintype "bidirectional"))
    )
    (net (code "144") (name "unconnected-(U$12-INT3-Pad23)") (class "Default")
      (node (ref "U$12") (pin "23") (pinfunction "INT3_23") (pintype "bidirectional"))
    )
    (net (code "145") (name "unconnected-(U$13-INT-Pad2)") (class "Default")
      (node (ref "U$13") (pin "2") (pinfunction "INT_2") (pintype "bidirectional"))
    )
    (net (code "146") (name "unconnected-(U$13-INT1-Pad9)") (class "Default")
      (node (ref "U$13") (pin "9") (pinfunction "INT1_9") (pintype "bidirectional"))
    )
    (net (code "147") (name "unconnected-(U$13-INT2-Pad16)") (class "Default")
      (node (ref "U$13") (pin "16") (pinfunction "INT2_16") (pintype "bidirectional"))
    )
    (net (code "148") (name "unconnected-(U$13-INT3-Pad23)") (class "Default")
      (node (ref "U$13") (pin "23") (pinfunction "INT3_23") (pintype "bidirectional"))
    )
    (net (code "149") (name "unconnected-(U$14-INT-Pad2)") (class "Default")
      (node (ref "U$14") (pin "2") (pinfunction "INT_2") (pintype "bidirectional"))
    )
    (net (code "150") (name "unconnected-(U$14-INT1-Pad9)") (class "Default")
      (node (ref "U$14") (pin "9") (pinfunction "INT1_9") (pintype "bidirectional"))
    )
    (net (code "151") (name "unconnected-(U$14-INT2-Pad16)") (class "Default")
      (node (ref "U$14") (pin "16") (pinfunction "INT2_16") (pintype "bidirectional"))
    )
    (net (code "152") (name "unconnected-(U$14-INT3-Pad23)") (class "Default")
      (node (ref "U$14") (pin "23") (pinfunction "INT3_23") (pintype "bidirectional"))
    )
    (net (code "153") (name "unconnected-(U$15-INT-Pad2)") (class "Default")
      (node (ref "U$15") (pin "2") (pinfunction "INT_2") (pintype "bidirectional"))
    )
    (net (code "154") (name "unconnected-(U$15-INT1-Pad9)") (class "Default")
      (node (ref "U$15") (pin "9") (pinfunction "INT1_9") (pintype "bidirectional"))
    )
    (net (code "155") (name "unconnected-(U$15-INT2-Pad16)") (class "Default")
      (node (ref "U$15") (pin "16") (pinfunction "INT2_16") (pintype "bidirectional"))
    )
    (net (code "156") (name "unconnected-(U$15-INT3-Pad23)") (class "Default")
      (node (ref "U$15") (pin "23") (pinfunction "INT3_23") (pintype "bidirectional"))
    )
    (net (code "157") (name "unconnected-(U$16-INT-Pad2)") (class "Default")
      (node (ref "U$16") (pin "2") (pinfunction "INT_2") (pintype "bidirectional"))
    )
    (net (code "158") (name "unconnected-(U$16-INT1-Pad9)") (class "Default")
      (node (ref "U$16") (pin "9") (pinfunction "INT1_9") (pintype "bidirectional"))
    )
    (net (code "159") (name "unconnected-(U$16-INT2-Pad16)") (class "Default")
      (node (ref "U$16") (pin "16") (pinfunction "INT2_16") (pintype "bidirectional"))
    )
    (net (code "160") (name "unconnected-(U$16-INT3-Pad23)") (class "Default")
      (node (ref "U$16") (pin "23") (pinfunction "INT3_23") (pintype "bidirectional"))
    )
    (net (code "161") (name "unconnected-(U$17-INT-Pad2)") (class "Default")
      (node (ref "U$17") (pin "2") (pinfunction "INT_2") (pintype "bidirectional"))
    )
    (net (code "162") (name "unconnected-(U$17-INT1-Pad9)") (class "Default")
      (node (ref "U$17") (pin "9") (pinfunction "INT1_9") (pintype "bidirectional"))
    )
    (net (code "163") (name "unconnected-(U$17-INT2-Pad16)") (class "Default")
      (node (ref "U$17") (pin "16") (pinfunction "INT2_16") (pintype "bidirectional"))
    )
    (net (code "164") (name "unconnected-(U$17-INT3-Pad23)") (class "Default")
      (node (ref "U$17") (pin "23") (pinfunction "INT3_23") (pintype "bidirectional"))
    )
    (net (code "165") (name "unconnected-(U$18-INT-Pad2)") (class "Default")
      (node (ref "U$18") (pin "2") (pinfunction "INT_2") (pintype "bidirectional"))
    )
    (net (code "166") (name "unconnected-(U$18-INT1-Pad9)") (class "Default")
      (node (ref "U$18") (pin "9") (pinfunction "INT1_9") (pintype "bidirectional"))
    )
    (net (code "167") (name "unconnected-(U$18-INT2-Pad16)") (class "Default")
      (node (ref "U$18") (pin "16") (pinfunction "INT2_16") (pintype "bidirectional"))
    )
    (net (code "168") (name "unconnected-(U$18-INT3-Pad23)") (class "Default")
      (node (ref "U$18") (pin "23") (pinfunction "INT3_23") (pintype "bidirectional"))
    )
    (net (code "169") (name "unconnected-(U$19-INT-Pad2)") (class "Default")
      (node (ref "U$19") (pin "2") (pinfunction "INT_2") (pintype "bidirectional"))
    )
    (net (code "170") (name "unconnected-(U$19-INT1-Pad9)") (class "Default")
      (node (ref "U$19") (pin "9") (pinfunction "INT1_9") (pintype "bidirectional"))
    )
    (net (code "171") (name "unconnected-(U$19-INT2-Pad16)") (class "Default")
      (node (ref "U$19") (pin "16") (pinfunction "INT2_16") (pintype "bidirectional"))
    )
    (net (code "172") (name "unconnected-(U$19-INT3-Pad23)") (class "Default")
      (node (ref "U$19") (pin "23") (pinfunction "INT3_23") (pintype "bidirectional"))
    )
    (net (code "173") (name "unconnected-(U$20-INT-Pad2)") (class "Default")
      (node (ref "U$20") (pin "2") (pinfunction "INT_2") (pintype "bidirectional"))
    )
    (net (code "174") (name "unconnected-(U$20-INT1-Pad9)") (class "Default")
      (node (ref "U$20") (pin "9") (pinfunction "INT1_9") (pintype "bidirectional"))
    )
    (net (code "175") (name "unconnected-(U$20-INT2-Pad16)") (class "Default")
      (node (ref "U$20") (pin "16") (pinfunction "INT2_16") (pintype "bidirectional"))
    )
    (net (code "176") (name "unconnected-(U$20-INT3-Pad23)") (class "Default")
      (node (ref "U$20") (pin "23") (pinfunction "INT3_23") (pintype "bidirectional"))
    )
    (net (code "177") (name "unconnected-(U$21-INT-Pad2)") (class "Default")
      (node (ref "U$21") (pin "2") (pinfunction "INT_2") (pintype "bidirectional"))
    )
    (net (code "178") (name "unconnected-(U$21-INT1-Pad9)") (class "Default")
      (node (ref "U$21") (pin "9") (pinfunction "INT1_9") (pintype "bidirectional"))
    )
    (net (code "179") (name "unconnected-(U$21-INT2-Pad16)") (class "Default")
      (node (ref "U$21") (pin "16") (pinfunction "INT2_16") (pintype "bidirectional"))
    )
    (net (code "180") (name "unconnected-(U$21-INT3-Pad23)") (class "Default")
      (node (ref "U$21") (pin "23") (pinfunction "INT3_23") (pintype "bidirectional"))
    )
    (net (code "181") (name "unconnected-(U$22-INT-Pad2)") (class "Default")
      (node (ref "U$22") (pin "2") (pinfunction "INT_2") (pintype "bidirectional"))
    )
    (net (code "182") (name "unconnected-(U$22-INT1-Pad9)") (class "Default")
      (node (ref "U$22") (pin "9") (pinfunction "INT1_9") (pintype "bidirectional"))
    )
    (net (code "183") (name "unconnected-(U$22-INT2-Pad16)") (class "Default")
      (node (ref "U$22") (pin "16") (pinfunction "INT2_16") (pintype "bidirectional"))
    )
    (net (code "184") (name "unconnected-(U$22-INT3-Pad23)") (class "Default")
      (node (ref "U$22") (pin "23") (pinfunction "INT3_23") (pintype "bidirectional"))
    )
    (net (code "185") (name "unconnected-(U$23-INT-Pad2)") (class "Default")
      (node (ref "U$23") (pin "2") (pinfunction "INT_2") (pintype "bidirectional"))
    )
    (net (code "186") (name "unconnected-(U$23-INT1-Pad9)") (class "Default")
      (node (ref "U$23") (pin "9") (pinfunction "INT1_9") (pintype "bidirectional"))
    )
    (net (code "187") (name "unconnected-(U$23-INT2-Pad16)") (class "Default")
      (node (ref "U$23") (pin "16") (pinfunction "INT2_16") (pintype "bidirectional"))
    )
    (net (code "188") (name "unconnected-(U$23-INT3-Pad23)") (class "Default")
      (node (ref "U$23") (pin "23") (pinfunction "INT3_23") (pintype "bidirectional"))
    )
    (net (code "189") (name "unconnected-(U$24-INT-Pad2)") (class "Default")
      (node (ref "U$24") (pin "2") (pinfunction "INT_2") (pintype "bidirectional"))
    )
    (net (code "190") (name "unconnected-(U$24-INT1-Pad9)") (class "Default")
      (node (ref "U$24") (pin "9") (pinfunction "INT1_9") (pintype "bidirectional"))
    )
    (net (code "191") (name "unconnected-(U$24-INT2-Pad16)") (class "Default")
      (node (ref "U$24") (pin "16") (pinfunction "INT2_16") (pintype "bidirectional"))
    )
    (net (code "192") (name "unconnected-(U$24-INT3-Pad23)") (class "Default")
      (node (ref "U$24") (pin "23") (pinfunction "INT3_23") (pintype "bidirectional"))
    )
    (net (code "193") (name "unconnected-(U$25-P$5-Pad5)") (class "Default")
      (node (ref "U$25") (pin "5") (pinfunction "P$5_5") (pintype "bidirectional"))
    )
    (net (code "194") (name "unconnected-(U$26-NIC-Pad41)") (class "Default")
      (node (ref "U$26") (pin "41") (pinfunction "NIC_41") (pintype "bidirectional"))
    )
    (net (code "195") (name "unconnected-(U$26-NIC-Pad42)") (class "Default")
      (node (ref "U$26") (pin "42") (pinfunction "NIC_42") (pintype "bidirectional"))
    )
    (net (code "196") (name "unconnected-(U$26-NIC-Pad44)") (class "Default")
      (node (ref "U$26") (pin "44") (pinfunction "NIC_44") (pintype "bidirectional"))
    )
    (net (code "197") (name "unconnected-(U$26-S13-Pad48)") (class "Default")
      (node (ref "U$26") (pin "48") (pinfunction "S13_48") (pintype "bidirectional"))
    )
    (net (code "198") (name "unconnected-(U$26-S14-Pad47)") (class "Default")
      (node (ref "U$26") (pin "47") (pinfunction "S14_47") (pintype "bidirectional"))
    )
    (net (code "199") (name "unconnected-(U$26-S15-Pad46)") (class "Default")
      (node (ref "U$26") (pin "46") (pinfunction "S15_46") (pintype "bidirectional"))
    )
    (net (code "200") (name "unconnected-(U$26-S16-Pad45)") (class "Default")
      (node (ref "U$26") (pin "45") (pinfunction "S16_45") (pintype "bidirectional"))
    )
    (net (code "201") (name "unconnected-(U$26-S29-Pad37)") (class "Default")
      (node (ref "U$26") (pin "37") (pinfunction "S29_37") (pintype "bidirectional"))
    )
    (net (code "202") (name "unconnected-(U$26-S30-Pad38)") (class "Default")
      (node (ref "U$26") (pin "38") (pinfunction "S30_38") (pintype "bidirectional"))
    )
    (net (code "203") (name "unconnected-(U$26-S31-Pad39)") (class "Default")
      (node (ref "U$26") (pin "39") (pinfunction "S31_39") (pintype "bidirectional"))
    )
    (net (code "204") (name "unconnected-(U$26-S32-Pad40)") (class "Default")
      (node (ref "U$26") (pin "40") (pinfunction "S32_40") (pintype "bidirectional"))
    )
    (net (code "205") (name "unconnected-(U$27-NIC-Pad41)") (class "Default")
      (node (ref "U$27") (pin "41") (pinfunction "NIC_41") (pintype "bidirectional"))
    )
    (net (code "206") (name "unconnected-(U$27-NIC-Pad42)") (class "Default")
      (node (ref "U$27") (pin "42") (pinfunction "NIC_42") (pintype "bidirectional"))
    )
    (net (code "207") (name "unconnected-(U$27-NIC-Pad44)") (class "Default")
      (node (ref "U$27") (pin "44") (pinfunction "NIC_44") (pintype "bidirectional"))
    )
    (net (code "208") (name "unconnected-(U$27-S13-Pad48)") (class "Default")
      (node (ref "U$27") (pin "48") (pinfunction "S13_48") (pintype "bidirectional"))
    )
    (net (code "209") (name "unconnected-(U$27-S14-Pad47)") (class "Default")
      (node (ref "U$27") (pin "47") (pinfunction "S14_47") (pintype "bidirectional"))
    )
    (net (code "210") (name "unconnected-(U$27-S15-Pad46)") (class "Default")
      (node (ref "U$27") (pin "46") (pinfunction "S15_46") (pintype "bidirectional"))
    )
    (net (code "211") (name "unconnected-(U$27-S16-Pad45)") (class "Default")
      (node (ref "U$27") (pin "45") (pinfunction "S16_45") (pintype "bidirectional"))
    )
    (net (code "212") (name "unconnected-(U$27-S29-Pad37)") (class "Default")
      (node (ref "U$27") (pin "37") (pinfunction "S29_37") (pintype "bidirectional"))
    )
    (net (code "213") (name "unconnected-(U$27-S30-Pad38)") (class "Default")
      (node (ref "U$27") (pin "38") (pinfunction "S30_38") (pintype "bidirectional"))
    )
    (net (code "214") (name "unconnected-(U$27-S31-Pad39)") (class "Default")
      (node (ref "U$27") (pin "39") (pinfunction "S31_39") (pintype "bidirectional"))
    )
    (net (code "215") (name "unconnected-(U$27-S32-Pad40)") (class "Default")
      (node (ref "U$27") (pin "40") (pinfunction "S32_40") (pintype "bidirectional"))
    )
    (net (code "216") (name "unconnected-(U$28-P$1-Pad1)") (class "Default")
      (node (ref "U$28") (pin "1") (pinfunction "P$1_1") (pintype "bidirectional"))
    )
    (net (code "217") (name "unconnected-(U$28-P$3-Pad3)") (class "Default")
      (node (ref "U$28") (pin "3") (pinfunction "P$3_3") (pintype "bidirectional"))
    )
    (net (code "218") (name "unconnected-(U$28-P$4-Pad4)") (class "Default")
      (node (ref "U$28") (pin "4") (pinfunction "P$4_4") (pintype "bidirectional"))
    )
  )
)
